# I2CRJ45X16.net
KiCad netlist of a schematic drawn in EAGLE
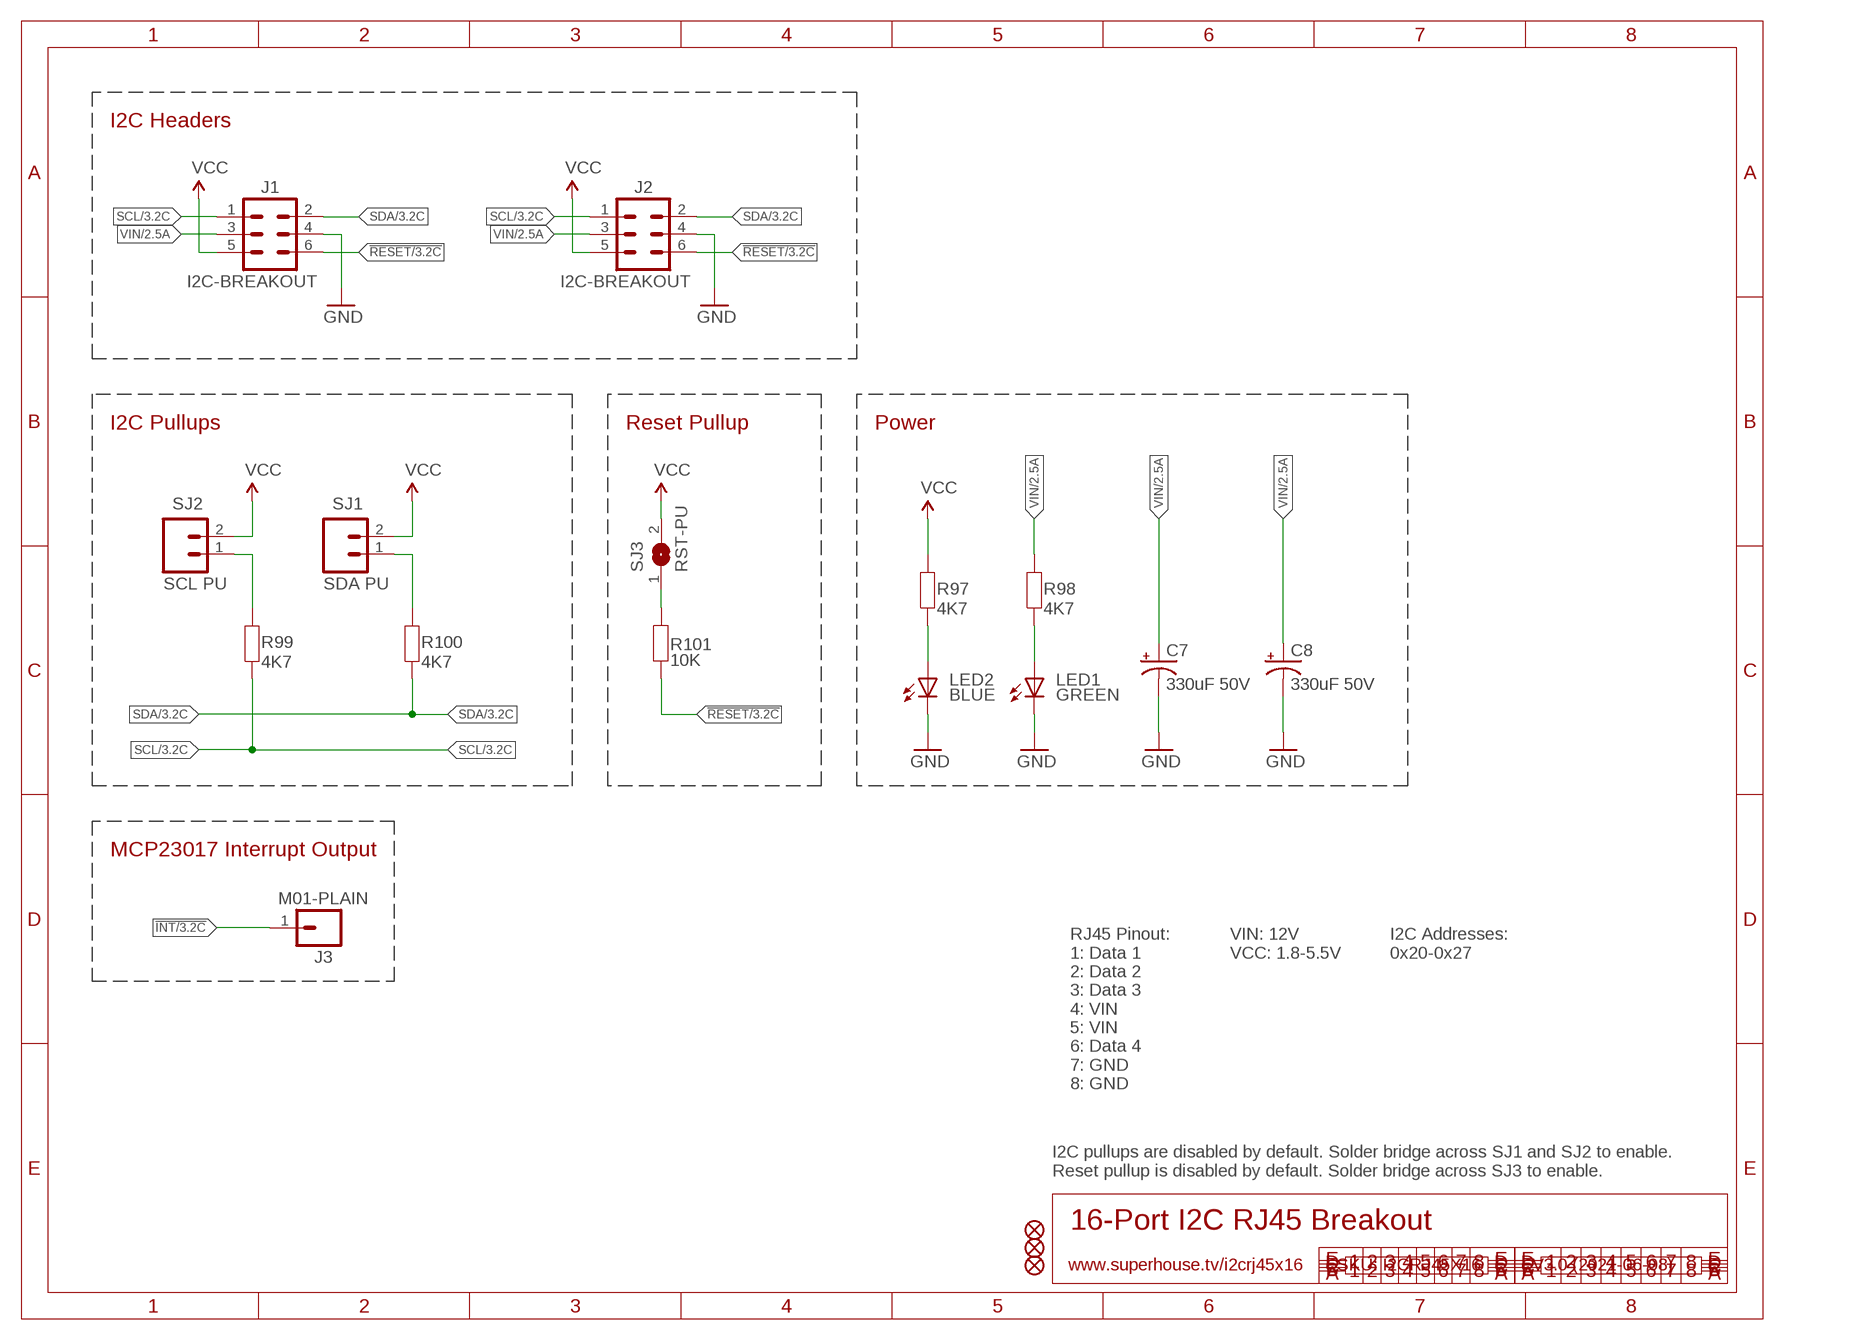
[diagram p0: schematic, sheet 1]
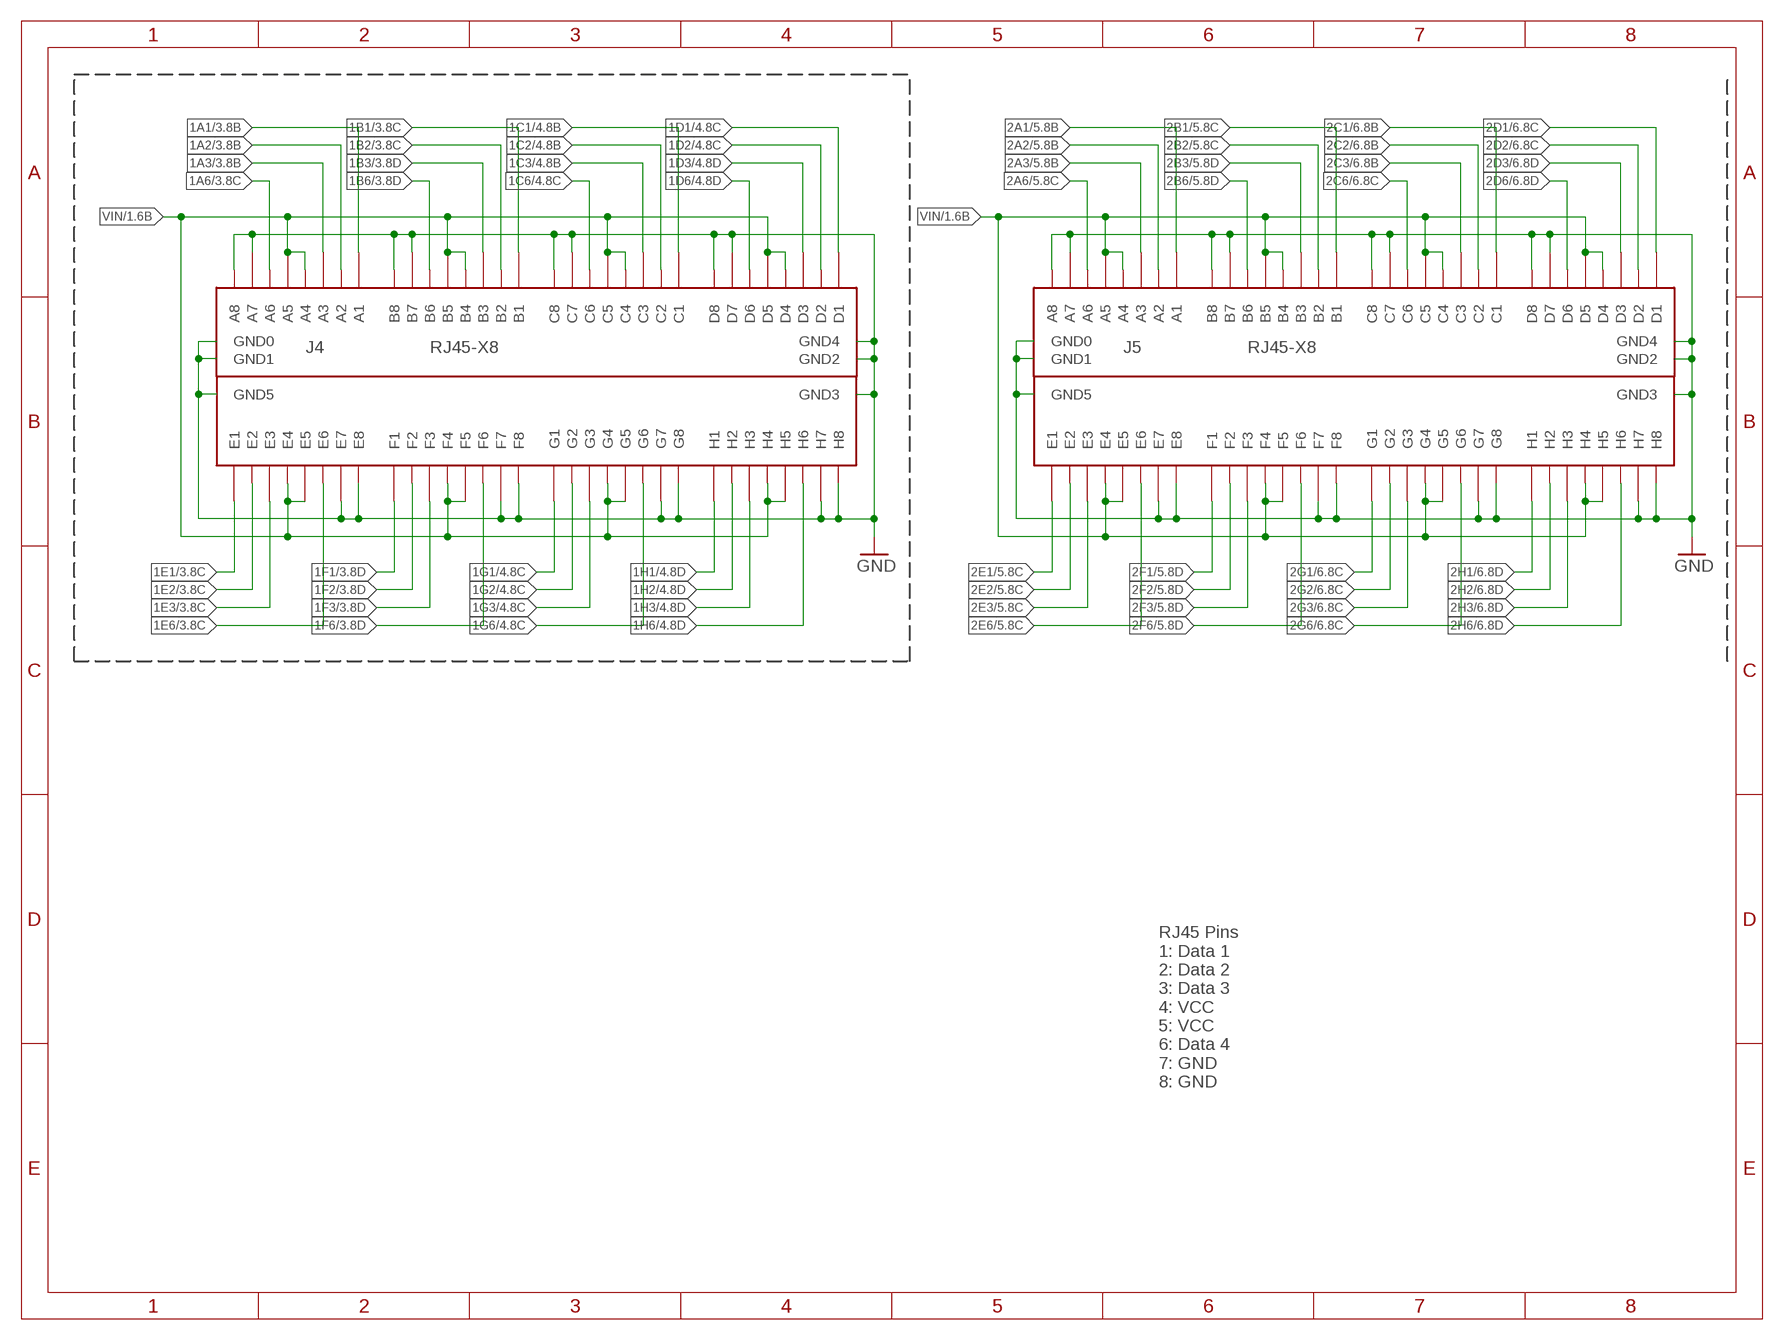
[diagram p1: schematic, sheet 2]
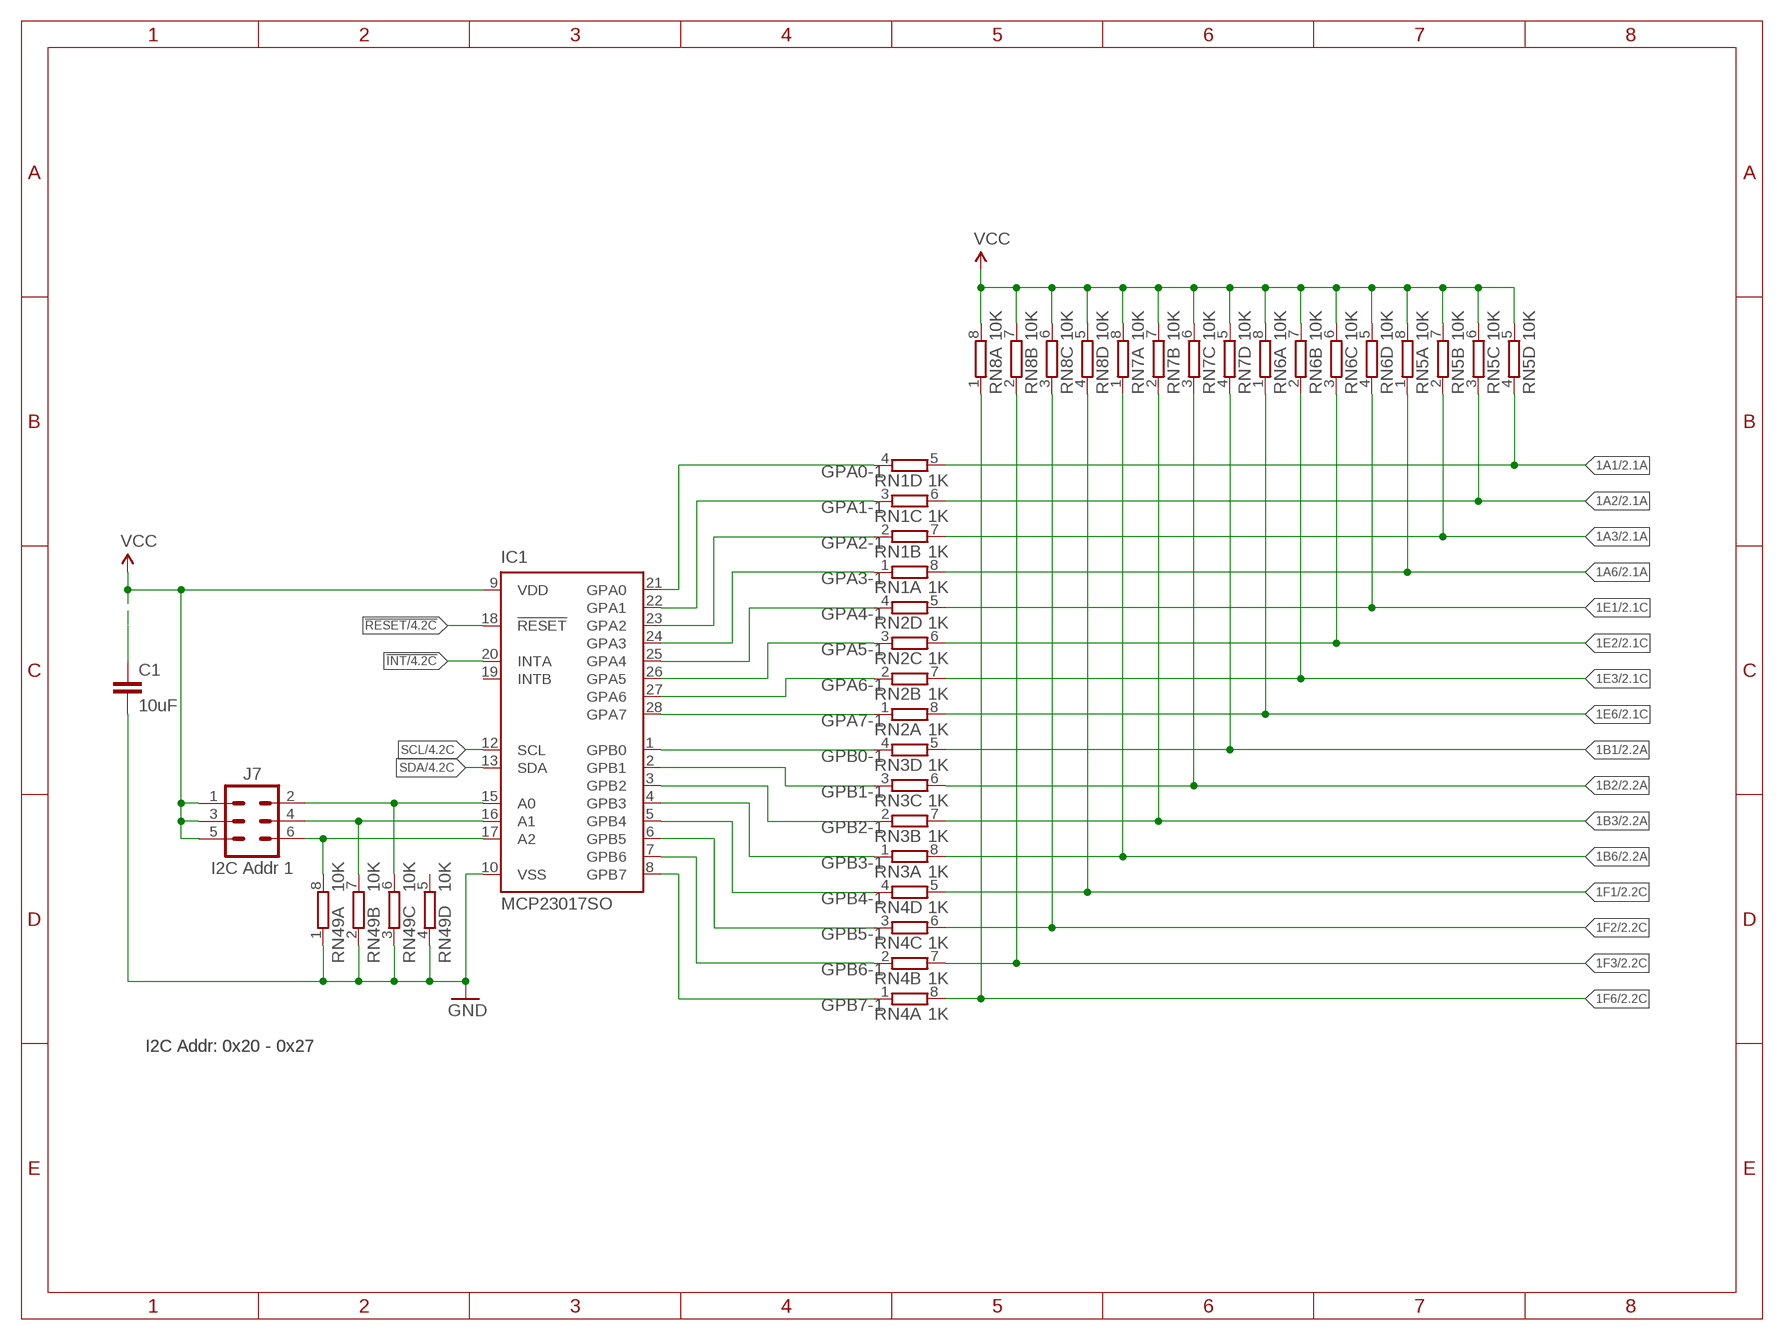
[diagram p2: schematic, sheet 3]
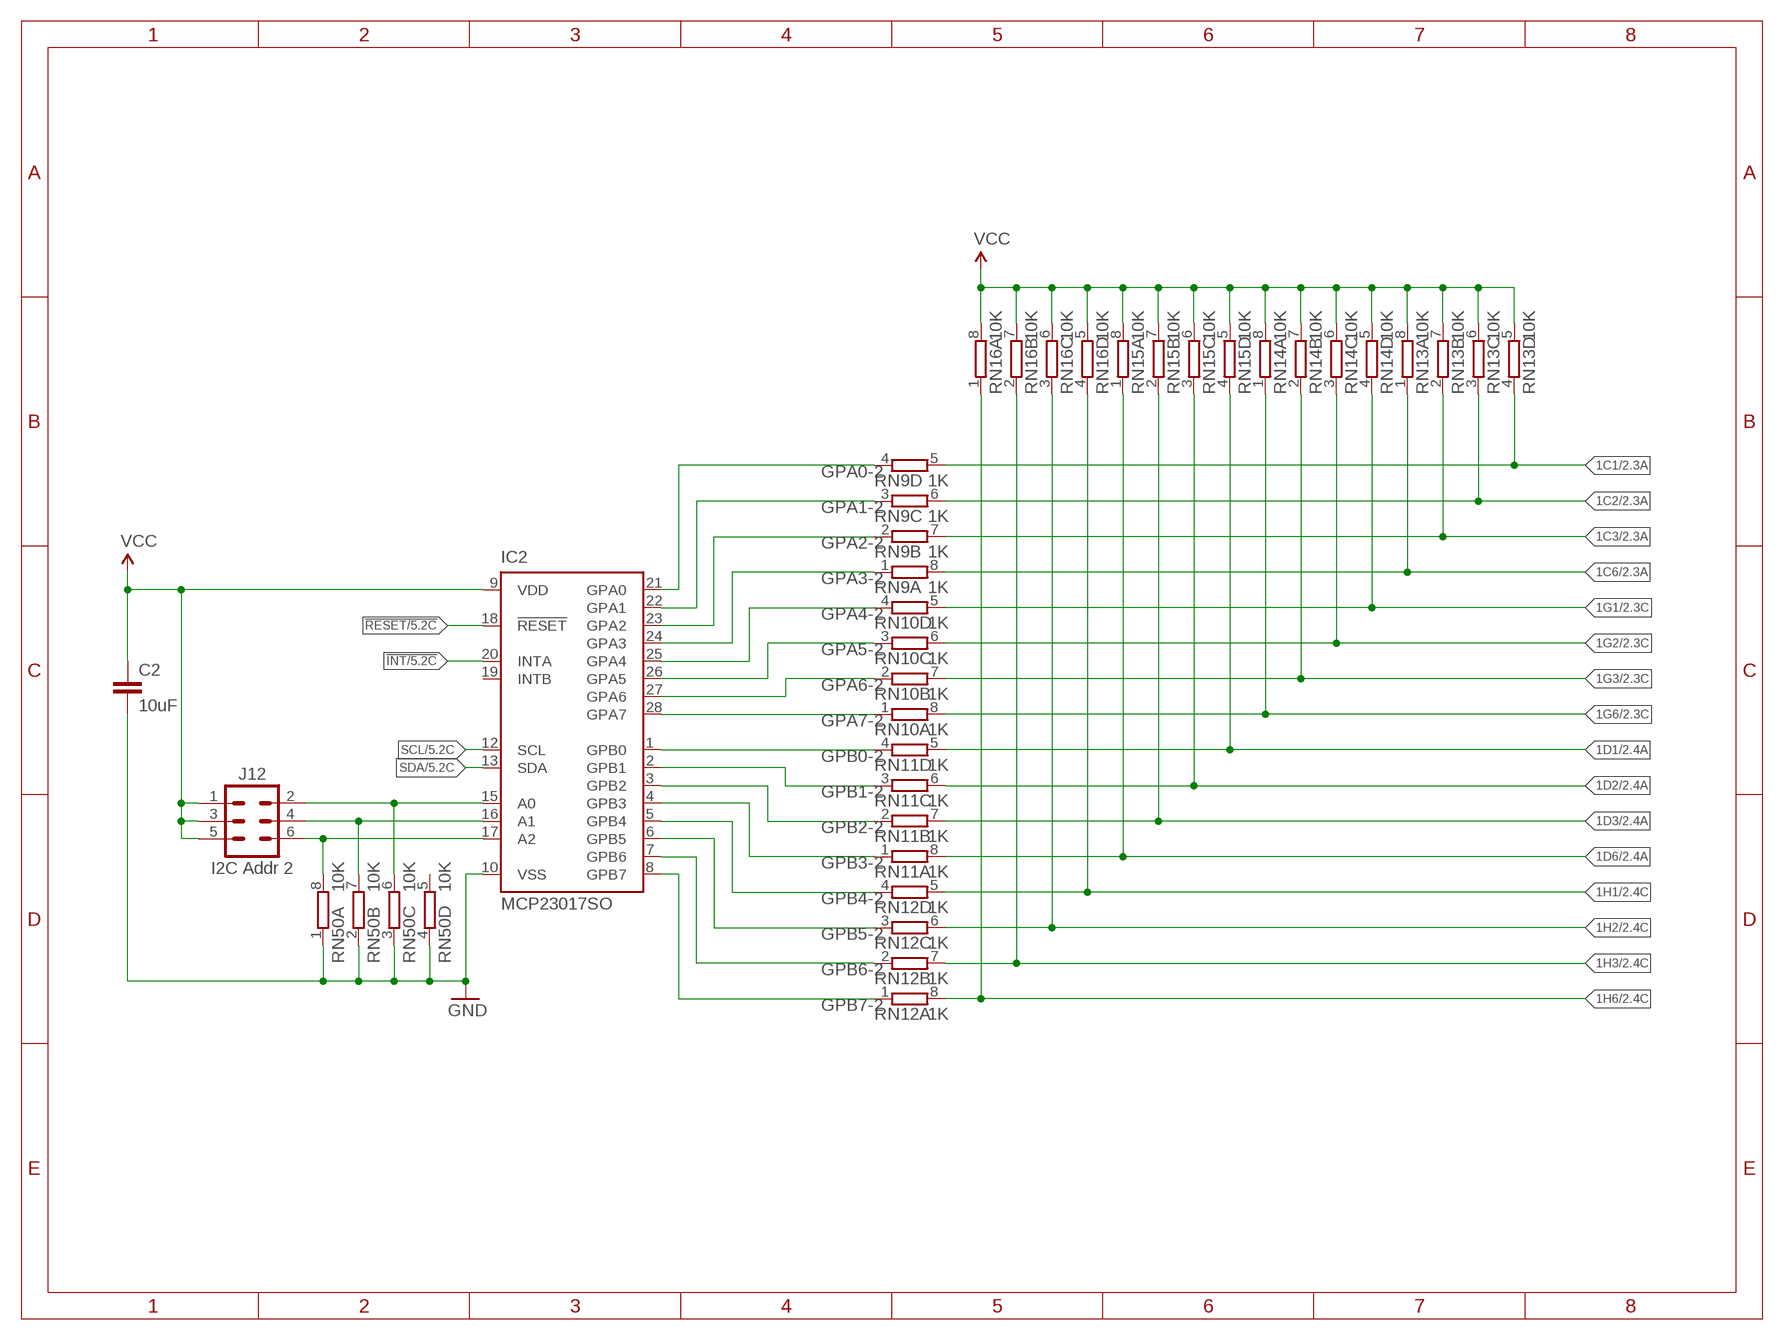
[diagram p3: schematic, sheet 4]
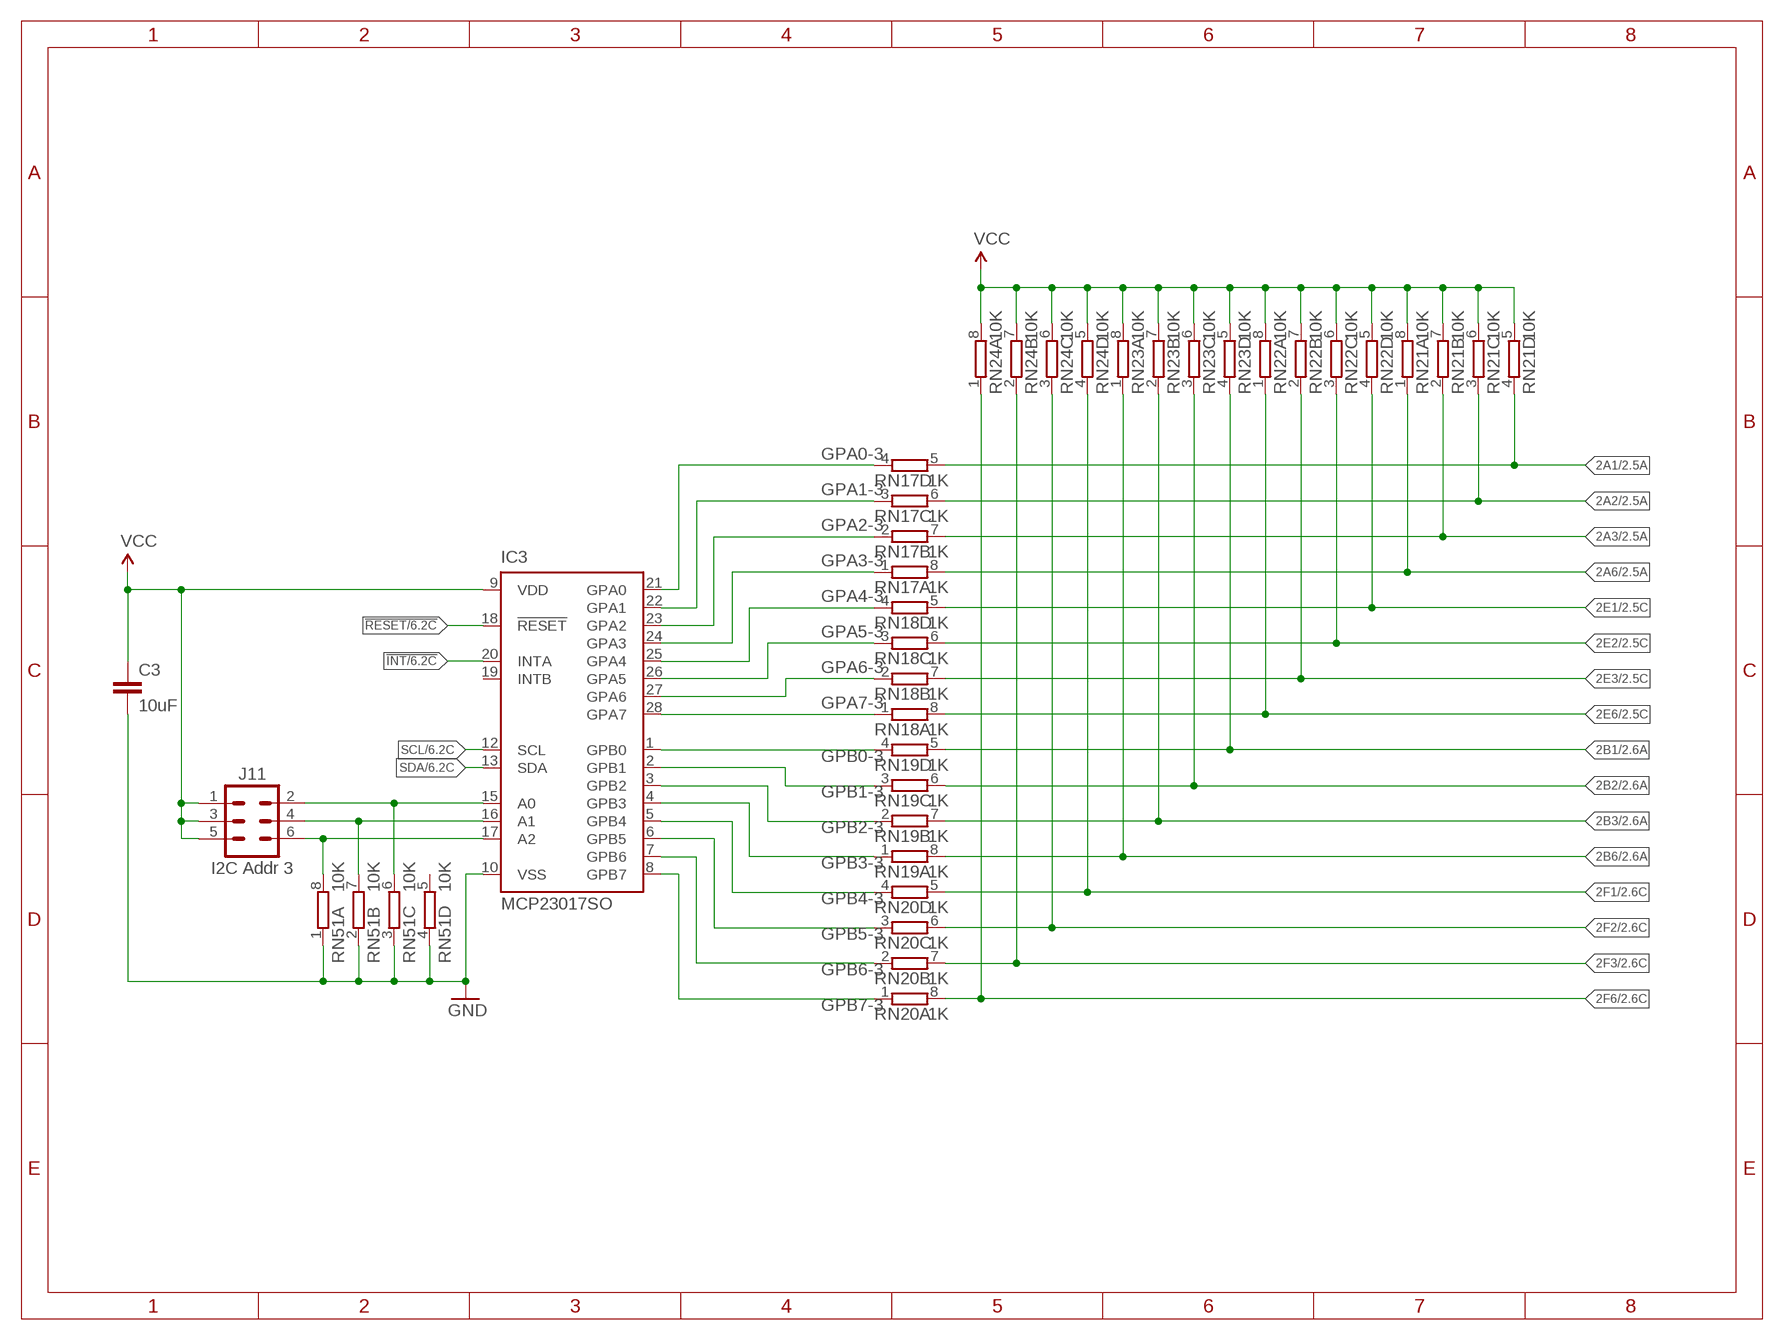
[diagram p4: schematic, sheet 5]
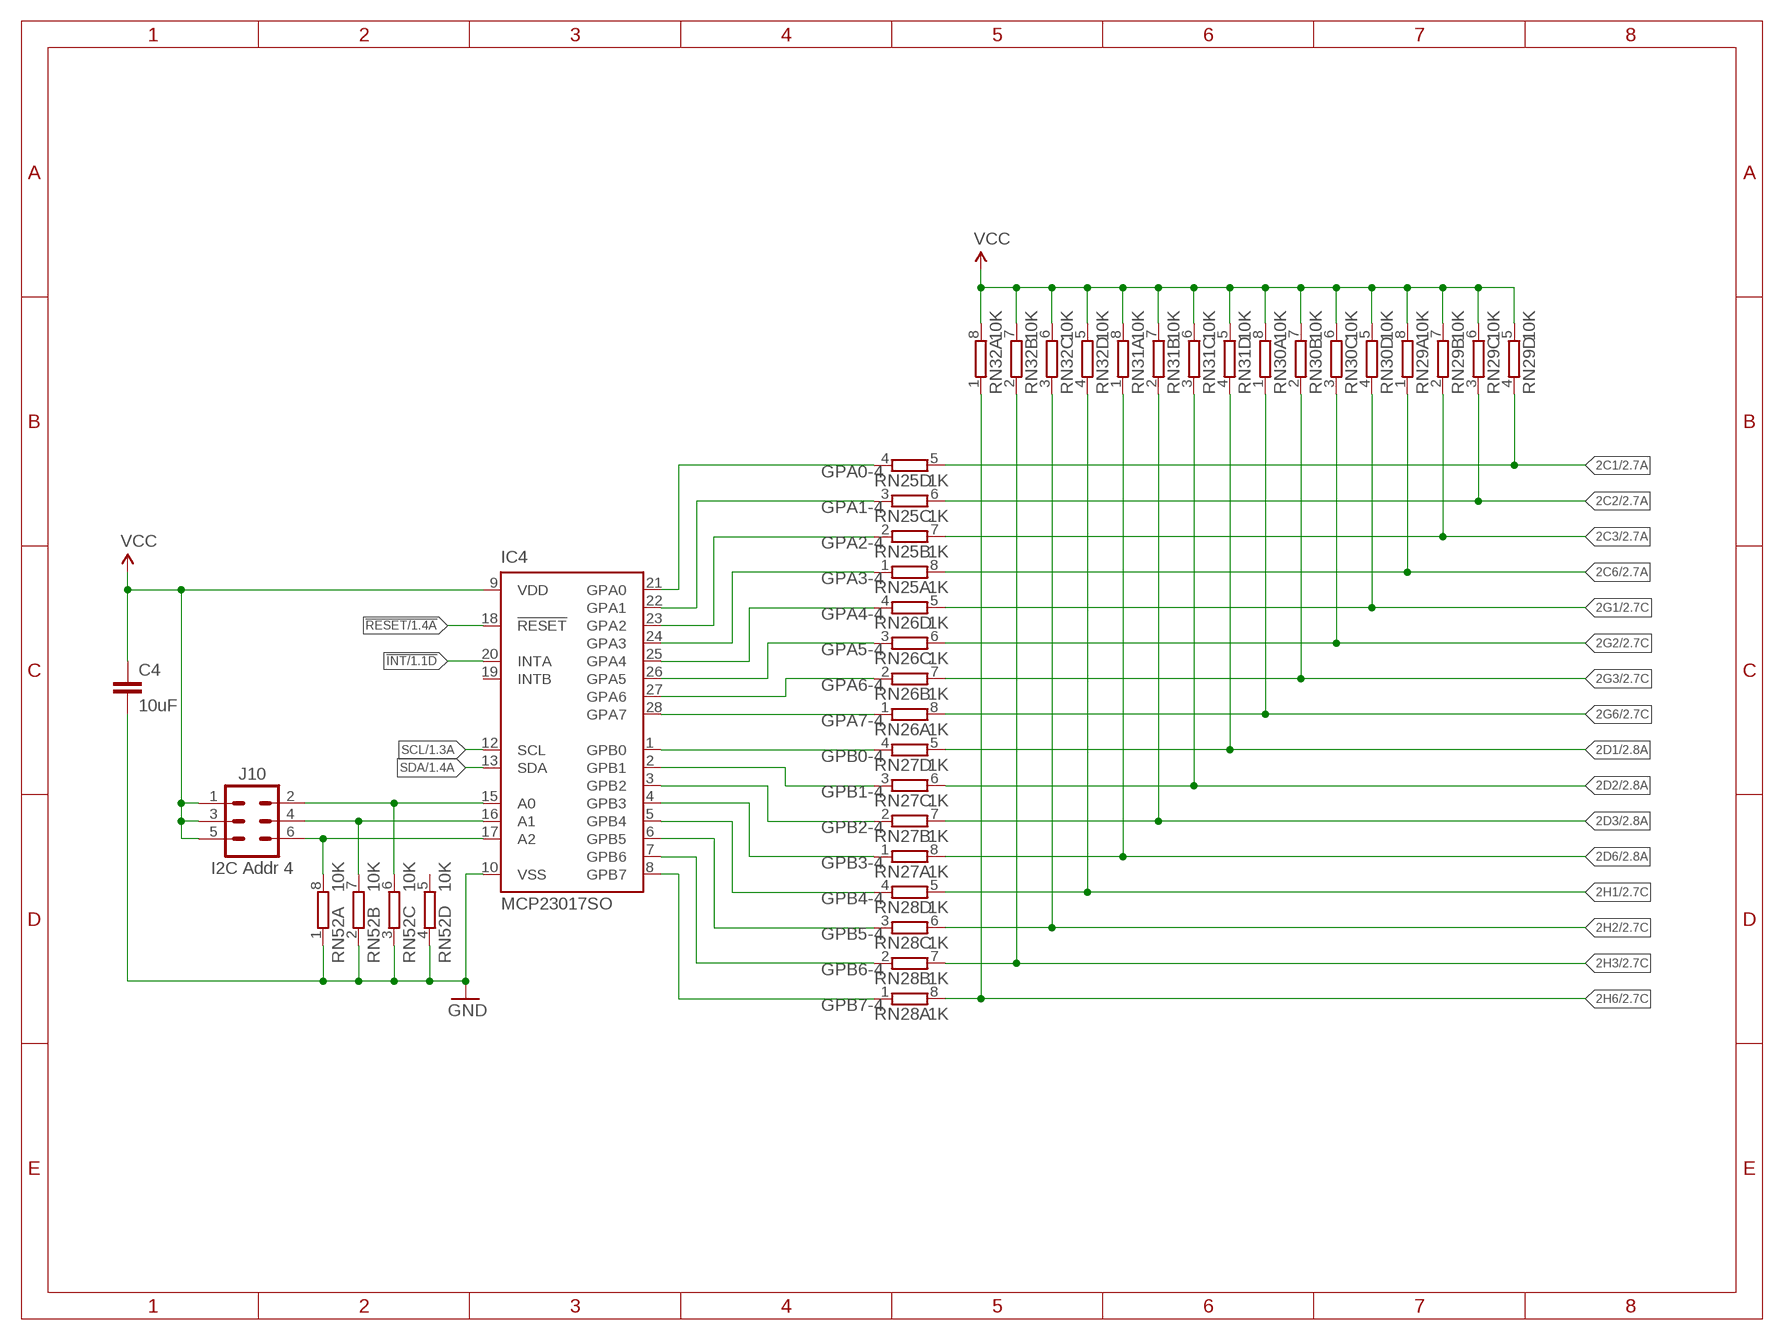
[diagram p5: schematic, sheet 6]

(export (version "E")
  (design (tool "Eeschema 10.0.6"))
  (components
    (comp (ref "C3")
      (value "10uF")
      (footprint "eagle-import:C0805")
      (libsource (lib "eagle-import") (part "CAP0805"))
    )
    (comp (ref "IC3")
      (value "MCP23017SO")
      (footprint "eagle-import:SO28W")
      (libsource (lib "eagle-import") (part "MCP23017SO"))
    )
    (comp (ref "J11")
      (value "I2C Addr 3")
      (footprint "eagle-import:2X03-P")
      (libsource (lib "eagle-import") (part "M02X3-PIN"))
    )
    (comp (ref "RN17")
      (value "1K")
      (footprint "eagle-import:CAY16")
      (libsource (lib "eagle-import") (part "4R-NCAY16"))
    )
    (comp (ref "RN18")
      (value "1K")
      (footprint "eagle-import:CAY16")
      (libsource (lib "eagle-import") (part "4R-NCAY16"))
    )
    (comp (ref "RN19")
      (value "1K")
      (footprint "eagle-import:CAY16")
      (libsource (lib "eagle-import") (part "4R-NCAY16"))
    )
    (comp (ref "RN20")
      (value "1K")
      (footprint "eagle-import:CAY16")
      (libsource (lib "eagle-import") (part "4R-NCAY16"))
    )
    (comp (ref "RN21")
      (value "10K")
      (footprint "eagle-import:CAY16")
      (libsource (lib "eagle-import") (part "4R-NCAY16"))
    )
    (comp (ref "RN22")
      (value "10K")
      (footprint "eagle-import:CAY16")
      (libsource (lib "eagle-import") (part "4R-NCAY16"))
    )
    (comp (ref "RN23")
      (value "10K")
      (footprint "eagle-import:CAY16")
      (libsource (lib "eagle-import") (part "4R-NCAY16"))
    )
    (comp (ref "RN24")
      (value "10K")
      (footprint "eagle-import:CAY16")
      (libsource (lib "eagle-import") (part "4R-NCAY16"))
    )
    (comp (ref "RN51")
      (value "10K")
      (footprint "eagle-import:CAY16")
      (libsource (lib "eagle-import") (part "4R-NCAY16"))
    )
    (comp (ref "C4")
      (value "10uF")
      (footprint "eagle-import:C0805")
      (libsource (lib "eagle-import") (part "CAP0805"))
    )
    (comp (ref "IC4")
      (value "MCP23017SO")
      (footprint "eagle-import:SO28W")
      (libsource (lib "eagle-import") (part "MCP23017SO"))
    )
    (comp (ref "J10")
      (value "I2C Addr 4")
      (footprint "eagle-import:2X03-P")
      (libsource (lib "eagle-import") (part "M02X3-PIN"))
    )
    (comp (ref "RN25")
      (value "1K")
      (footprint "eagle-import:CAY16")
      (libsource (lib "eagle-import") (part "4R-NCAY16"))
    )
    (comp (ref "RN26")
      (value "1K")
      (footprint "eagle-import:CAY16")
      (libsource (lib "eagle-import") (part "4R-NCAY16"))
    )
    (comp (ref "RN27")
      (value "1K")
      (footprint "eagle-import:CAY16")
      (libsource (lib "eagle-import") (part "4R-NCAY16"))
    )
    (comp (ref "RN28")
      (value "1K")
      (footprint "eagle-import:CAY16")
      (libsource (lib "eagle-import") (part "4R-NCAY16"))
    )
    (comp (ref "RN29")
      (value "10K")
      (footprint "eagle-import:CAY16")
      (libsource (lib "eagle-import") (part "4R-NCAY16"))
    )
    (comp (ref "RN30")
      (value "10K")
      (footprint "eagle-import:CAY16")
      (libsource (lib "eagle-import") (part "4R-NCAY16"))
    )
    (comp (ref "RN31")
      (value "10K")
      (footprint "eagle-import:CAY16")
      (libsource (lib "eagle-import") (part "4R-NCAY16"))
    )
    (comp (ref "RN32")
      (value "10K")
      (footprint "eagle-import:CAY16")
      (libsource (lib "eagle-import") (part "4R-NCAY16"))
    )
    (comp (ref "RN52")
      (value "10K")
      (footprint "eagle-import:CAY16")
      (libsource (lib "eagle-import") (part "4R-NCAY16"))
    )
    (comp (ref "C7")
      (value "330uF 50V")
      (footprint "eagle-import:PANASONIC_G")
      (libsource (lib "eagle-import") (part "CAP_POLG"))
    )
    (comp (ref "C8")
      (value "330uF 50V")
      (footprint "eagle-import:PANASONIC_G")
      (libsource (lib "eagle-import") (part "CAP_POLG"))
    )
    (comp (ref "FID1")
      (value "FIDUCIAL1X2.5")
      (footprint "eagle-import:FIDUCIAL-1X2.5")
      (libsource (lib "eagle-import") (part "FIDUCIAL1X2.5"))
    )
    (comp (ref "FID2")
      (value "FIDUCIAL1X2.5")
      (footprint "eagle-import:FIDUCIAL-1X2.5")
      (libsource (lib "eagle-import") (part "FIDUCIAL1X2.5"))
    )
    (comp (ref "FID3")
      (value "FIDUCIAL1X2.5")
      (footprint "eagle-import:FIDUCIAL-1X2.5")
      (libsource (lib "eagle-import") (part "FIDUCIAL1X2.5"))
    )
    (comp (ref "J1")
      (value "I2C-BREAKOUT")
      (footprint "eagle-import:2X3-2.54-SHROUDED")
      (libsource (lib "eagle-import") (part "M02X3-SHROUDED"))
    )
    (comp (ref "J2")
      (value "I2C-BREAKOUT")
      (footprint "eagle-import:2X3-2.54-SHROUDED")
      (libsource (lib "eagle-import") (part "M02X3-SHROUDED"))
    )
    (comp (ref "J3")
      (value "M01-PLAIN")
      (footprint "eagle-import:1X01")
      (libsource (lib "eagle-import") (part "M01-PLAIN"))
    )
    (comp (ref "LED1")
      (value "GREEN")
      (footprint "eagle-import:LED-0603")
      (libsource (lib "eagle-import") (part "LED0603"))
    )
    (comp (ref "LED2")
      (value "BLUE")
      (footprint "eagle-import:LED-0603")
      (libsource (lib "eagle-import") (part "LED0603"))
    )
    (comp (ref "R97")
      (value "4K7")
      (footprint "eagle-import:R0603")
      (libsource (lib "eagle-import") (part "RESISTOR0603"))
    )
    (comp (ref "R98")
      (value "4K7")
      (footprint "eagle-import:R0603")
      (libsource (lib "eagle-import") (part "RESISTOR0603"))
    )
    (comp (ref "R99")
      (value "4K7")
      (footprint "eagle-import:R0603")
      (libsource (lib "eagle-import") (part "RESISTOR0603"))
    )
    (comp (ref "R100")
      (value "4K7")
      (footprint "eagle-import:R0603")
      (libsource (lib "eagle-import") (part "RESISTOR0603"))
    )
    (comp (ref "R101")
      (value "10K")
      (footprint "eagle-import:R0603")
      (libsource (lib "eagle-import") (part "RESISTOR0603"))
    )
    (comp (ref "SJ1")
      (value "SDA PU")
      (footprint "eagle-import:1X02-P")
      (libsource (lib "eagle-import") (part "M02-PIN"))
    )
    (comp (ref "SJ2")
      (value "SCL PU")
      (footprint "eagle-import:1X02-P")
      (libsource (lib "eagle-import") (part "M02-PIN"))
    )
    (comp (ref "SJ3")
      (value "RST-PU")
      (footprint "eagle-import:SJ")
      (libsource (lib "eagle-import") (part "SJ-NORMAL"))
    )
    (comp (ref "C2")
      (value "10uF")
      (footprint "eagle-import:C0805")
      (libsource (lib "eagle-import") (part "CAP0805"))
    )
    (comp (ref "IC2")
      (value "MCP23017SO")
      (footprint "eagle-import:SO28W")
      (libsource (lib "eagle-import") (part "MCP23017SO"))
    )
    (comp (ref "J12")
      (value "I2C Addr 2")
      (footprint "eagle-import:2X03-P")
      (libsource (lib "eagle-import") (part "M02X3-PIN"))
    )
    (comp (ref "RN9")
      (value "1K")
      (footprint "eagle-import:CAY16")
      (libsource (lib "eagle-import") (part "4R-NCAY16"))
    )
    (comp (ref "RN10")
      (value "1K")
      (footprint "eagle-import:CAY16")
      (libsource (lib "eagle-import") (part "4R-NCAY16"))
    )
    (comp (ref "RN11")
      (value "1K")
      (footprint "eagle-import:CAY16")
      (libsource (lib "eagle-import") (part "4R-NCAY16"))
    )
    (comp (ref "RN12")
      (value "1K")
      (footprint "eagle-import:CAY16")
      (libsource (lib "eagle-import") (part "4R-NCAY16"))
    )
    (comp (ref "RN13")
      (value "10K")
      (footprint "eagle-import:CAY16")
      (libsource (lib "eagle-import") (part "4R-NCAY16"))
    )
    (comp (ref "RN14")
      (value "10K")
      (footprint "eagle-import:CAY16")
      (libsource (lib "eagle-import") (part "4R-NCAY16"))
    )
    (comp (ref "RN15")
      (value "10K")
      (footprint "eagle-import:CAY16")
      (libsource (lib "eagle-import") (part "4R-NCAY16"))
    )
    (comp (ref "RN16")
      (value "10K")
      (footprint "eagle-import:CAY16")
      (libsource (lib "eagle-import") (part "4R-NCAY16"))
    )
    (comp (ref "RN50")
      (value "10K")
      (footprint "eagle-import:CAY16")
      (libsource (lib "eagle-import") (part "4R-NCAY16"))
    )
    (comp (ref "C1")
      (value "10uF")
      (footprint "eagle-import:C0805")
      (libsource (lib "eagle-import") (part "CAP0805"))
    )
    (comp (ref "IC1")
      (value "MCP23017SO")
      (footprint "eagle-import:SO28W")
      (libsource (lib "eagle-import") (part "MCP23017SO"))
    )
    (comp (ref "J7")
      (value "I2C Addr 1")
      (footprint "eagle-import:2X03-P")
      (libsource (lib "eagle-import") (part "M02X3-PIN"))
    )
    (comp (ref "RN1")
      (value "1K")
      (footprint "eagle-import:CAY16")
      (libsource (lib "eagle-import") (part "4R-NCAY16"))
    )
    (comp (ref "RN2")
      (value "1K")
      (footprint "eagle-import:CAY16")
      (libsource (lib "eagle-import") (part "4R-NCAY16"))
    )
    (comp (ref "RN3")
      (value "1K")
      (footprint "eagle-import:CAY16")
      (libsource (lib "eagle-import") (part "4R-NCAY16"))
    )
    (comp (ref "RN4")
      (value "1K")
      (footprint "eagle-import:CAY16")
      (libsource (lib "eagle-import") (part "4R-NCAY16"))
    )
    (comp (ref "RN5")
      (value "10K")
      (footprint "eagle-import:CAY16")
      (libsource (lib "eagle-import") (part "4R-NCAY16"))
    )
    (comp (ref "RN6")
      (value "10K")
      (footprint "eagle-import:CAY16")
      (libsource (lib "eagle-import") (part "4R-NCAY16"))
    )
    (comp (ref "RN7")
      (value "10K")
      (footprint "eagle-import:CAY16")
      (libsource (lib "eagle-import") (part "4R-NCAY16"))
    )
    (comp (ref "RN8")
      (value "10K")
      (footprint "eagle-import:CAY16")
      (libsource (lib "eagle-import") (part "4R-NCAY16"))
    )
    (comp (ref "RN49")
      (value "10K")
      (footprint "eagle-import:CAY16")
      (libsource (lib "eagle-import") (part "4R-NCAY16"))
    )
    (comp (ref "J4")
      (value "RJ45-X8")
      (footprint "eagle-import:RJ45-2X4")
      (libsource (lib "eagle-import") (part "RJ45-X8"))
    )
    (comp (ref "J5")
      (value "RJ45-X8")
      (footprint "eagle-import:RJ45-2X4")
      (libsource (lib "eagle-import") (part "RJ45-X8"))
    )
  )
  (nets
    (net (code "1") (name "1A1") (class "Default")
      (node (ref "J4") (pin "A1") (pinfunction "A1_A1") (pintype "bidirectional"))
      (node (ref "RN1") (pin "5") (pinfunction "2_5") (pintype "passive"))
      (node (ref "RN5") (pin "4") (pinfunction "1_4") (pintype "passive"))
    )
    (net (code "2") (name "1A2") (class "Default")
      (node (ref "J4") (pin "A2") (pinfunction "A2_A2") (pintype "bidirectional"))
      (node (ref "RN1") (pin "6") (pinfunction "2_6") (pintype "passive"))
      (node (ref "RN5") (pin "3") (pinfunction "1_3") (pintype "passive"))
    )
    (net (code "3") (name "1A3") (class "Default")
      (node (ref "J4") (pin "A3") (pinfunction "A3_A3") (pintype "bidirectional"))
      (node (ref "RN1") (pin "7") (pinfunction "2_7") (pintype "passive"))
      (node (ref "RN5") (pin "2") (pinfunction "1_2") (pintype "passive"))
    )
    (net (code "4") (name "1A6") (class "Default")
      (node (ref "J4") (pin "A6") (pinfunction "A6_A6") (pintype "bidirectional"))
      (node (ref "RN1") (pin "8") (pinfunction "2_8") (pintype "passive"))
      (node (ref "RN5") (pin "1") (pinfunction "1_1") (pintype "passive"))
    )
    (net (code "5") (name "1B1") (class "Default")
      (node (ref "J4") (pin "B1") (pinfunction "B1_B1") (pintype "bidirectional"))
      (node (ref "RN3") (pin "5") (pinfunction "2_5") (pintype "passive"))
      (node (ref "RN7") (pin "4") (pinfunction "1_4") (pintype "passive"))
    )
    (net (code "6") (name "1B2") (class "Default")
      (node (ref "J4") (pin "B2") (pinfunction "B2_B2") (pintype "bidirectional"))
      (node (ref "RN3") (pin "6") (pinfunction "2_6") (pintype "passive"))
      (node (ref "RN7") (pin "3") (pinfunction "1_3") (pintype "passive"))
    )
    (net (code "7") (name "1B3") (class "Default")
      (node (ref "J4") (pin "B3") (pinfunction "B3_B3") (pintype "bidirectional"))
      (node (ref "RN3") (pin "7") (pinfunction "2_7") (pintype "passive"))
      (node (ref "RN7") (pin "2") (pinfunction "1_2") (pintype "passive"))
    )
    (net (code "8") (name "1B6") (class "Default")
      (node (ref "J4") (pin "B6") (pinfunction "B6_B6") (pintype "bidirectional"))
      (node (ref "RN3") (pin "8") (pinfunction "2_8") (pintype "passive"))
      (node (ref "RN7") (pin "1") (pinfunction "1_1") (pintype "passive"))
    )
    (net (code "9") (name "1C1") (class "Default")
      (node (ref "J4") (pin "C1") (pinfunction "C1_C1") (pintype "bidirectional"))
      (node (ref "RN13") (pin "4") (pinfunction "1_4") (pintype "passive"))
      (node (ref "RN9") (pin "5") (pinfunction "2_5") (pintype "passive"))
    )
    (net (code "10") (name "1C2") (class "Default")
      (node (ref "J4") (pin "C2") (pinfunction "C2_C2") (pintype "bidirectional"))
      (node (ref "RN13") (pin "3") (pinfunction "1_3") (pintype "passive"))
      (node (ref "RN9") (pin "6") (pinfunction "2_6") (pintype "passive"))
    )
    (net (code "11") (name "1C3") (class "Default")
      (node (ref "J4") (pin "C3") (pinfunction "C3_C3") (pintype "bidirectional"))
      (node (ref "RN13") (pin "2") (pinfunction "1_2") (pintype "passive"))
      (node (ref "RN9") (pin "7") (pinfunction "2_7") (pintype "passive"))
    )
    (net (code "12") (name "1C6") (class "Default")
      (node (ref "J4") (pin "C6") (pinfunction "C6_C6") (pintype "bidirectional"))
      (node (ref "RN13") (pin "1") (pinfunction "1_1") (pintype "passive"))
      (node (ref "RN9") (pin "8") (pinfunction "2_8") (pintype "passive"))
    )
    (net (code "13") (name "1D1") (class "Default")
      (node (ref "J4") (pin "D1") (pinfunction "D1_D1") (pintype "bidirectional"))
      (node (ref "RN11") (pin "5") (pinfunction "2_5") (pintype "passive"))
      (node (ref "RN15") (pin "4") (pinfunction "1_4") (pintype "passive"))
    )
    (net (code "14") (name "1D2") (class "Default")
      (node (ref "J4") (pin "D2") (pinfunction "D2_D2") (pintype "bidirectional"))
      (node (ref "RN11") (pin "6") (pinfunction "2_6") (pintype "passive"))
      (node (ref "RN15") (pin "3") (pinfunction "1_3") (pintype "passive"))
    )
    (net (code "15") (name "1D3") (class "Default")
      (node (ref "J4") (pin "D3") (pinfunction "D3_D3") (pintype "bidirectional"))
      (node (ref "RN11") (pin "7") (pinfunction "2_7") (pintype "passive"))
      (node (ref "RN15") (pin "2") (pinfunction "1_2") (pintype "passive"))
    )
    (net (code "16") (name "1D6") (class "Default")
      (node (ref "J4") (pin "D6") (pinfunction "D6_D6") (pintype "bidirectional"))
      (node (ref "RN11") (pin "8") (pinfunction "2_8") (pintype "passive"))
      (node (ref "RN15") (pin "1") (pinfunction "1_1") (pintype "passive"))
    )
    (net (code "17") (name "1E1") (class "Default")
      (node (ref "J4") (pin "E1") (pinfunction "E1_E1") (pintype "bidirectional"))
      (node (ref "RN2") (pin "5") (pinfunction "2_5") (pintype "passive"))
      (node (ref "RN6") (pin "4") (pinfunction "1_4") (pintype "passive"))
    )
    (net (code "18") (name "1E2") (class "Default")
      (node (ref "J4") (pin "E2") (pinfunction "E2_E2") (pintype "bidirectional"))
      (node (ref "RN2") (pin "6") (pinfunction "2_6") (pintype "passive"))
      (node (ref "RN6") (pin "3") (pinfunction "1_3") (pintype "passive"))
    )
    (net (code "19") (name "1E3") (class "Default")
      (node (ref "J4") (pin "E3") (pinfunction "E3_E3") (pintype "bidirectional"))
      (node (ref "RN2") (pin "7") (pinfunction "2_7") (pintype "passive"))
      (node (ref "RN6") (pin "2") (pinfunction "1_2") (pintype "passive"))
    )
    (net (code "20") (name "1E6") (class "Default")
      (node (ref "J4") (pin "E6") (pinfunction "E6_E6") (pintype "bidirectional"))
      (node (ref "RN2") (pin "8") (pinfunction "2_8") (pintype "passive"))
      (node (ref "RN6") (pin "1") (pinfunction "1_1") (pintype "passive"))
    )
    (net (code "21") (name "1F1") (class "Default")
      (node (ref "J4") (pin "F1") (pinfunction "F1_F1") (pintype "bidirectional"))
      (node (ref "RN4") (pin "5") (pinfunction "2_5") (pintype "passive"))
      (node (ref "RN8") (pin "4") (pinfunction "1_4") (pintype "passive"))
    )
    (net (code "22") (name "1F2") (class "Default")
      (node (ref "J4") (pin "F2") (pinfunction "F2_F2") (pintype "bidirectional"))
      (node (ref "RN4") (pin "6") (pinfunction "2_6") (pintype "passive"))
      (node (ref "RN8") (pin "3") (pinfunction "1_3") (pintype "passive"))
    )
    (net (code "23") (name "1F3") (class "Default")
      (node (ref "J4") (pin "F3") (pinfunction "F3_F3") (pintype "bidirectional"))
      (node (ref "RN4") (pin "7") (pinfunction "2_7") (pintype "passive"))
      (node (ref "RN8") (pin "2") (pinfunction "1_2") (pintype "passive"))
    )
    (net (code "24") (name "1F6") (class "Default")
      (node (ref "J4") (pin "F6") (pinfunction "F6_F6") (pintype "bidirectional"))
      (node (ref "RN4") (pin "8") (pinfunction "2_8") (pintype "passive"))
      (node (ref "RN8") (pin "1") (pinfunction "1_1") (pintype "passive"))
    )
    (net (code "25") (name "1G1") (class "Default")
      (node (ref "J4") (pin "G1") (pinfunction "G1_G1") (pintype "bidirectional"))
      (node (ref "RN10") (pin "5") (pinfunction "2_5") (pintype "passive"))
      (node (ref "RN14") (pin "4") (pinfunction "1_4") (pintype "passive"))
    )
    (net (code "26") (name "1G2") (class "Default")
      (node (ref "J4") (pin "G2") (pinfunction "G2_G2") (pintype "bidirectional"))
      (node (ref "RN10") (pin "6") (pinfunction "2_6") (pintype "passive"))
      (node (ref "RN14") (pin "3") (pinfunction "1_3") (pintype "passive"))
    )
    (net (code "27") (name "1G3") (class "Default")
      (node (ref "J4") (pin "G3") (pinfunction "G3_G3") (pintype "bidirectional"))
      (node (ref "RN10") (pin "7") (pinfunction "2_7") (pintype "passive"))
      (node (ref "RN14") (pin "2") (pinfunction "1_2") (pintype "passive"))
    )
    (net (code "28") (name "1G6") (class "Default")
      (node (ref "J4") (pin "G6") (pinfunction "G6_G6") (pintype "bidirectional"))
      (node (ref "RN10") (pin "8") (pinfunction "2_8") (pintype "passive"))
      (node (ref "RN14") (pin "1") (pinfunction "1_1") (pintype "passive"))
    )
    (net (code "29") (name "1H1") (class "Default")
      (node (ref "J4") (pin "H1") (pinfunction "H1_H1") (pintype "bidirectional"))
      (node (ref "RN12") (pin "5") (pinfunction "2_5") (pintype "passive"))
      (node (ref "RN16") (pin "4") (pinfunction "1_4") (pintype "passive"))
    )
    (net (code "30") (name "1H2") (class "Default")
      (node (ref "J4") (pin "H2") (pinfunction "H2_H2") (pintype "bidirectional"))
      (node (ref "RN12") (pin "6") (pinfunction "2_6") (pintype "passive"))
      (node (ref "RN16") (pin "3") (pinfunction "1_3") (pintype "passive"))
    )
    (net (code "31") (name "1H3") (class "Default")
      (node (ref "J4") (pin "H3") (pinfunction "H3_H3") (pintype "bidirectional"))
      (node (ref "RN12") (pin "7") (pinfunction "2_7") (pintype "passive"))
      (node (ref "RN16") (pin "2") (pinfunction "1_2") (pintype "passive"))
    )
    (net (code "32") (name "1H6") (class "Default")
      (node (ref "J4") (pin "H6") (pinfunction "H6_H6") (pintype "bidirectional"))
      (node (ref "RN12") (pin "8") (pinfunction "2_8") (pintype "passive"))
      (node (ref "RN16") (pin "1") (pinfunction "1_1") (pintype "passive"))
    )
    (net (code "33") (name "2A1") (class "Default")
      (node (ref "J5") (pin "A1") (pinfunction "A1_A1") (pintype "bidirectional"))
      (node (ref "RN17") (pin "5") (pinfunction "2_5") (pintype "passive"))
      (node (ref "RN21") (pin "4") (pinfunction "1_4") (pintype "passive"))
    )
    (net (code "34") (name "2A2") (class "Default")
      (node (ref "J5") (pin "A2") (pinfunction "A2_A2") (pintype "bidirectional"))
      (node (ref "RN17") (pin "6") (pinfunction "2_6") (pintype "passive"))
      (node (ref "RN21") (pin "3") (pinfunction "1_3") (pintype "passive"))
    )
    (net (code "35") (name "2A3") (class "Default")
      (node (ref "J5") (pin "A3") (pinfunction "A3_A3") (pintype "bidirectional"))
      (node (ref "RN17") (pin "7") (pinfunction "2_7") (pintype "passive"))
      (node (ref "RN21") (pin "2") (pinfunction "1_2") (pintype "passive"))
    )
    (net (code "36") (name "2A6") (class "Default")
      (node (ref "J5") (pin "A6") (pinfunction "A6_A6") (pintype "bidirectional"))
      (node (ref "RN17") (pin "8") (pinfunction "2_8") (pintype "passive"))
      (node (ref "RN21") (pin "1") (pinfunction "1_1") (pintype "passive"))
    )
    (net (code "37") (name "2B1") (class "Default")
      (node (ref "J5") (pin "B1") (pinfunction "B1_B1") (pintype "bidirectional"))
      (node (ref "RN19") (pin "5") (pinfunction "2_5") (pintype "passive"))
      (node (ref "RN23") (pin "4") (pinfunction "1_4") (pintype "passive"))
    )
    (net (code "38") (name "2B2") (class "Default")
      (node (ref "J5") (pin "B2") (pinfunction "B2_B2") (pintype "bidirectional"))
      (node (ref "RN19") (pin "6") (pinfunction "2_6") (pintype "passive"))
      (node (ref "RN23") (pin "3") (pinfunction "1_3") (pintype "passive"))
    )
    (net (code "39") (name "2B3") (class "Default")
      (node (ref "J5") (pin "B3") (pinfunction "B3_B3") (pintype "bidirectional"))
      (node (ref "RN19") (pin "7") (pinfunction "2_7") (pintype "passive"))
      (node (ref "RN23") (pin "2") (pinfunction "1_2") (pintype "passive"))
    )
    (net (code "40") (name "2B6") (class "Default")
      (node (ref "J5") (pin "B6") (pinfunction "B6_B6") (pintype "bidirectional"))
      (node (ref "RN19") (pin "8") (pinfunction "2_8") (pintype "passive"))
      (node (ref "RN23") (pin "1") (pinfunction "1_1") (pintype "passive"))
    )
    (net (code "41") (name "2C1") (class "Default")
      (node (ref "J5") (pin "C1") (pinfunction "C1_C1") (pintype "bidirectional"))
      (node (ref "RN25") (pin "5") (pinfunction "2_5") (pintype "passive"))
      (node (ref "RN29") (pin "4") (pinfunction "1_4") (pintype "passive"))
    )
    (net (code "42") (name "2C2") (class "Default")
      (node (ref "J5") (pin "C2") (pinfunction "C2_C2") (pintype "bidirectional"))
      (node (ref "RN25") (pin "6") (pinfunction "2_6") (pintype "passive"))
      (node (ref "RN29") (pin "3") (pinfunction "1_3") (pintype "passive"))
    )
    (net (code "43") (name "2C3") (class "Default")
      (node (ref "J5") (pin "C3") (pinfunction "C3_C3") (pintype "bidirectional"))
      (node (ref "RN25") (pin "7") (pinfunction "2_7") (pintype "passive"))
      (node (ref "RN29") (pin "2") (pinfunction "1_2") (pintype "passive"))
    )
    (net (code "44") (name "2C6") (class "Default")
      (node (ref "J5") (pin "C6") (pinfunction "C6_C6") (pintype "bidirectional"))
      (node (ref "RN25") (pin "8") (pinfunction "2_8") (pintype "passive"))
      (node (ref "RN29") (pin "1") (pinfunction "1_1") (pintype "passive"))
    )
    (net (code "45") (name "2D1") (class "Default")
      (node (ref "J5") (pin "D1") (pinfunction "D1_D1") (pintype "bidirectional"))
      (node (ref "RN27") (pin "5") (pinfunction "2_5") (pintype "passive"))
      (node (ref "RN31") (pin "4") (pinfunction "1_4") (pintype "passive"))
    )
    (net (code "46") (name "2D2") (class "Default")
      (node (ref "J5") (pin "D2") (pinfunction "D2_D2") (pintype "bidirectional"))
      (node (ref "RN27") (pin "6") (pinfunction "2_6") (pintype "passive"))
      (node (ref "RN31") (pin "3") (pinfunction "1_3") (pintype "passive"))
    )
    (net (code "47") (name "2D3") (class "Default")
      (node (ref "J5") (pin "D3") (pinfunction "D3_D3") (pintype "bidirectional"))
      (node (ref "RN27") (pin "7") (pinfunction "2_7") (pintype "passive"))
      (node (ref "RN31") (pin "2") (pinfunction "1_2") (pintype "passive"))
    )
    (net (code "48") (name "2D6") (class "Default")
      (node (ref "J5") (pin "D6") (pinfunction "D6_D6") (pintype "bidirectional"))
      (node (ref "RN27") (pin "8") (pinfunction "2_8") (pintype "passive"))
      (node (ref "RN31") (pin "1") (pinfunction "1_1") (pintype "passive"))
    )
    (net (code "49") (name "2E1") (class "Default")
      (node (ref "J5") (pin "E1") (pinfunction "E1_E1") (pintype "bidirectional"))
      (node (ref "RN18") (pin "5") (pinfunction "2_5") (pintype "passive"))
      (node (ref "RN22") (pin "4") (pinfunction "1_4") (pintype "passive"))
    )
    (net (code "50") (name "2E2") (class "Default")
      (node (ref "J5") (pin "E2") (pinfunction "E2_E2") (pintype "bidirectional"))
      (node (ref "RN18") (pin "6") (pinfunction "2_6") (pintype "passive"))
      (node (ref "RN22") (pin "3") (pinfunction "1_3") (pintype "passive"))
    )
    (net (code "51") (name "2E3") (class "Default")
      (node (ref "J5") (pin "E3") (pinfunction "E3_E3") (pintype "bidirectional"))
      (node (ref "RN18") (pin "7") (pinfunction "2_7") (pintype "passive"))
      (node (ref "RN22") (pin "2") (pinfunction "1_2") (pintype "passive"))
    )
    (net (code "52") (name "2E6") (class "Default")
      (node (ref "J5") (pin "E6") (pinfunction "E6_E6") (pintype "bidirectional"))
      (node (ref "RN18") (pin "8") (pinfunction "2_8") (pintype "passive"))
      (node (ref "RN22") (pin "1") (pinfunction "1_1") (pintype "passive"))
    )
    (net (code "53") (name "2F1") (class "Default")
      (node (ref "J5") (pin "F1") (pinfunction "F1_F1") (pintype "bidirectional"))
      (node (ref "RN20") (pin "5") (pinfunction "2_5") (pintype "passive"))
      (node (ref "RN24") (pin "4") (pinfunction "1_4") (pintype "passive"))
    )
    (net (code "54") (name "2F2") (class "Default")
      (node (ref "J5") (pin "F2") (pinfunction "F2_F2") (pintype "bidirectional"))
      (node (ref "RN20") (pin "6") (pinfunction "2_6") (pintype "passive"))
      (node (ref "RN24") (pin "3") (pinfunction "1_3") (pintype "passive"))
    )
    (net (code "55") (name "2F3") (class "Default")
      (node (ref "J5") (pin "F3") (pinfunction "F3_F3") (pintype "bidirectional"))
      (node (ref "RN20") (pin "7") (pinfunction "2_7") (pintype "passive"))
      (node (ref "RN24") (pin "2") (pinfunction "1_2") (pintype "passive"))
    )
    (net (code "56") (name "2F6") (class "Default")
      (node (ref "J5") (pin "F6") (pinfunction "F6_F6") (pintype "bidirectional"))
      (node (ref "RN20") (pin "8") (pinfunction "2_8") (pintype "passive"))
      (node (ref "RN24") (pin "1") (pinfunction "1_1") (pintype "passive"))
    )
    (net (code "57") (name "2G1") (class "Default")
      (node (ref "J5") (pin "G1") (pinfunction "G1_G1") (pintype "bidirectional"))
      (node (ref "RN26") (pin "5") (pinfunction "2_5") (pintype "passive"))
      (node (ref "RN30") (pin "4") (pinfunction "1_4") (pintype "passive"))
    )
    (net (code "58") (name "2G2") (class "Default")
      (node (ref "J5") (pin "G2") (pinfunction "G2_G2") (pintype "bidirectional"))
      (node (ref "RN26") (pin "6") (pinfunction "2_6") (pintype "passive"))
      (node (ref "RN30") (pin "3") (pinfunction "1_3") (pintype "passive"))
    )
    (net (code "59") (name "2G3") (class "Default")
      (node (ref "J5") (pin "G3") (pinfunction "G3_G3") (pintype "bidirectional"))
      (node (ref "RN26") (pin "7") (pinfunction "2_7") (pintype "passive"))
      (node (ref "RN30") (pin "2") (pinfunction "1_2") (pintype "passive"))
    )
    (net (code "60") (name "2G6") (class "Default")
      (node (ref "J5") (pin "G6") (pinfunction "G6_G6") (pintype "bidirectional"))
      (node (ref "RN26") (pin "8") (pinfunction "2_8") (pintype "passive"))
      (node (ref "RN30") (pin "1") (pinfunction "1_1") (pintype "passive"))
    )
    (net (code "61") (name "2H1") (class "Default")
      (node (ref "J5") (pin "H1") (pinfunction "H1_H1") (pintype "bidirectional"))
      (node (ref "RN28") (pin "5") (pinfunction "2_5") (pintype "passive"))
      (node (ref "RN32") (pin "4") (pinfunction "1_4") (pintype "passive"))
    )
    (net (code "62") (name "2H2") (class "Default")
      (node (ref "J5") (pin "H2") (pinfunction "H2_H2") (pintype "bidirectional"))
      (node (ref "RN28") (pin "6") (pinfunction "2_6") (pintype "passive"))
      (node (ref "RN32") (pin "3") (pinfunction "1_3") (pintype "passive"))
    )
    (net (code "63") (name "2H3") (class "Default")
      (node (ref "J5") (pin "H3") (pinfunction "H3_H3") (pintype "bidirectional"))
      (node (ref "RN28") (pin "7") (pinfunction "2_7") (pintype "passive"))
      (node (ref "RN32") (pin "2") (pinfunction "1_2") (pintype "passive"))
    )
    (net (code "64") (name "2H6") (class "Default")
      (node (ref "J5") (pin "H6") (pinfunction "H6_H6") (pintype "bidirectional"))
      (node (ref "RN28") (pin "8") (pinfunction "2_8") (pintype "passive"))
      (node (ref "RN32") (pin "1") (pinfunction "1_1") (pintype "passive"))
    )
    (net (code "65") (name "GND") (class "Default")
      (node (ref "C1") (pin "2") (pinfunction "2_2") (pintype "passive"))
      (node (ref "C2") (pin "2") (pinfunction "2_2") (pintype "passive"))
      (node (ref "C3") (pin "2") (pinfunction "2_2") (pintype "passive"))
      (node (ref "C4") (pin "2") (pinfunction "2_2") (pintype "passive"))
      (node (ref "C7") (pin "-") (pinfunction "-_-") (pintype "passive"))
      (node (ref "C8") (pin "-") (pinfunction "-_-") (pintype "passive"))
      (node (ref "IC1") (pin "10") (pinfunction "VSS_10") (pintype "power_in"))
      (node (ref "IC2") (pin "10") (pinfunction "VSS_10") (pintype "power_in"))
      (node (ref "IC3") (pin "10") (pinfunction "VSS_10") (pintype "power_in"))
      (node (ref "IC4") (pin "10") (pinfunction "VSS_10") (pintype "power_in"))
      (node (ref "J1") (pin "4") (pinfunction "4_4") (pintype "passive"))
      (node (ref "J2") (pin "4") (pinfunction "4_4") (pintype "passive"))
      (node (ref "J4") (pin "A7") (pinfunction "A7_A7") (pintype "bidirectional"))
      (node (ref "J4") (pin "A8") (pinfunction "A8_A8") (pintype "bidirectional"))
      (node (ref "J4") (pin "B7") (pinfunction "B7_B7") (pintype "bidirectional"))
      (node (ref "J4") (pin "B8") (pinfunction "B8_B8") (pintype "bidirectional"))
      (node (ref "J4") (pin "C7") (pinfunction "C7_C7") (pintype "bidirectional"))
      (node (ref "J4") (pin "C8") (pinfunction "C8_C8") (pintype "bidirectional"))
      (node (ref "J4") (pin "D7") (pinfunction "D7_D7") (pintype "bidirectional"))
      (node (ref "J4") (pin "D8") (pinfunction "D8_D8") (pintype "bidirectional"))
      (node (ref "J4") (pin "E7") (pinfunction "E7_E7") (pintype "bidirectional"))
      (node (ref "J4") (pin "E8") (pinfunction "E8_E8") (pintype "bidirectional"))
      (node (ref "J4") (pin "F7") (pinfunction "F7_F7") (pintype "bidirectional"))
      (node (ref "J4") (pin "F8") (pinfunction "F8_F8") (pintype "bidirectional"))
      (node (ref "J4") (pin "G7") (pinfunction "G7_G7") (pintype "bidirectional"))
      (node (ref "J4") (pin "G8") (pinfunction "G8_G8") (pintype "bidirectional"))
      (node (ref "J4") (pin "GND0") (pinfunction "GND0_GND0") (pintype "power_in"))
      (node (ref "J4") (pin "GND1") (pinfunction "GND1_GND1") (pintype "power_in"))
      (node (ref "J4") (pin "GND2") (pinfunction "GND2_GND2") (pintype "power_in"))
      (node (ref "J4") (pin "GND3") (pinfunction "GND3_GND3") (pintype "power_in"))
      (node (ref "J4") (pin "GND4") (pinfunction "GND4_GND4") (pintype "power_in"))
      (node (ref "J4") (pin "GND5") (pinfunction "GND5_GND5") (pintype "power_in"))
      (node (ref "J4") (pin "H7") (pinfunction "H7_H7") (pintype "bidirectional"))
      (node (ref "J4") (pin "H8") (pinfunction "H8_H8") (pintype "bidirectional"))
      (node (ref "J5") (pin "A7") (pinfunction "A7_A7") (pintype "bidirectional"))
      (node (ref "J5") (pin "A8") (pinfunction "A8_A8") (pintype "bidirectional"))
      (node (ref "J5") (pin "B7") (pinfunction "B7_B7") (pintype "bidirectional"))
      (node (ref "J5") (pin "B8") (pinfunction "B8_B8") (pintype "bidirectional"))
      (node (ref "J5") (pin "C7") (pinfunction "C7_C7") (pintype "bidirectional"))
      (node (ref "J5") (pin "C8") (pinfunction "C8_C8") (pintype "bidirectional"))
      (node (ref "J5") (pin "D7") (pinfunction "D7_D7") (pintype "bidirectional"))
      (node (ref "J5") (pin "D8") (pinfunction "D8_D8") (pintype "bidirectional"))
      (node (ref "J5") (pin "E7") (pinfunction "E7_E7") (pintype "bidirectional"))
      (node (ref "J5") (pin "E8") (pinfunction "E8_E8") (pintype "bidirectional"))
      (node (ref "J5") (pin "F7") (pinfunction "F7_F7") (pintype "bidirectional"))
      (node (ref "J5") (pin "F8") (pinfunction "F8_F8") (pintype "bidirectional"))
      (node (ref "J5") (pin "G7") (pinfunction "G7_G7") (pintype "bidirectional"))
      (node (ref "J5") (pin "G8") (pinfunction "G8_G8") (pintype "bidirectional"))
      (node (ref "J5") (pin "GND0") (pinfunction "GND0_GND0") (pintype "power_in"))
      (node (ref "J5") (pin "GND1") (pinfunction "GND1_GND1") (pintype "power_in"))
      (node (ref "J5") (pin "GND2") (pinfunction "GND2_GND2") (pintype "power_in"))
      (node (ref "J5") (pin "GND3") (pinfunction "GND3_GND3") (pintype "power_in"))
      (node (ref "J5") (pin "GND4") (pinfunction "GND4_GND4") (pintype "power_in"))
      (node (ref "J5") (pin "GND5") (pinfunction "GND5_GND5") (pintype "power_in"))
      (node (ref "J5") (pin "H7") (pinfunction "H7_H7") (pintype "bidirectional"))
      (node (ref "J5") (pin "H8") (pinfunction "H8_H8") (pintype "bidirectional"))
      (node (ref "LED1") (pin "C") (pinfunction "C_C") (pintype "passive"))
      (node (ref "LED2") (pin "C") (pinfunction "C_C") (pintype "passive"))
      (node (ref "RN49") (pin "1") (pinfunction "1_1") (pintype "passive"))
      (node (ref "RN49") (pin "2") (pinfunction "1_2") (pintype "passive"))
      (node (ref "RN49") (pin "3") (pinfunction "1_3") (pintype "passive"))
      (node (ref "RN49") (pin "4") (pinfunction "1_4") (pintype "passive"))
      (node (ref "RN50") (pin "1") (pinfunction "1_1") (pintype "passive"))
      (node (ref "RN50") (pin "2") (pinfunction "1_2") (pintype "passive"))
      (node (ref "RN50") (pin "3") (pinfunction "1_3") (pintype "passive"))
      (node (ref "RN50") (pin "4") (pinfunction "1_4") (pintype "passive"))
      (node (ref "RN51") (pin "1") (pinfunction "1_1") (pintype "passive"))
      (node (ref "RN51") (pin "2") (pinfunction "1_2") (pintype "passive"))
      (node (ref "RN51") (pin "3") (pinfunction "1_3") (pintype "passive"))
      (node (ref "RN51") (pin "4") (pinfunction "1_4") (pintype "passive"))
      (node (ref "RN52") (pin "1") (pinfunction "1_1") (pintype "passive"))
      (node (ref "RN52") (pin "2") (pinfunction "1_2") (pintype "passive"))
      (node (ref "RN52") (pin "3") (pinfunction "1_3") (pintype "passive"))
      (node (ref "RN52") (pin "4") (pinfunction "1_4") (pintype "passive"))
    )
    (net (code "66") (name "GPA0-1") (class "Default")
      (node (ref "IC1") (pin "21") (pinfunction "GPA0_21") (pintype "bidirectional"))
      (node (ref "RN1") (pin "4") (pinfunction "1_4") (pintype "passive"))
    )
    (net (code "67") (name "GPA0-2") (class "Default")
      (node (ref "IC2") (pin "21") (pinfunction "GPA0_21") (pintype "bidirectional"))
      (node (ref "RN9") (pin "4") (pinfunction "1_4") (pintype "passive"))
    )
    (net (code "68") (name "GPA0-3") (class "Default")
      (node (ref "IC3") (pin "21") (pinfunction "GPA0_21") (pintype "bidirectional"))
      (node (ref "RN17") (pin "4") (pinfunction "1_4") (pintype "passive"))
    )
    (net (code "69") (name "GPA0-4") (class "Default")
      (node (ref "IC4") (pin "21") (pinfunction "GPA0_21") (pintype "bidirectional"))
      (node (ref "RN25") (pin "4") (pinfunction "1_4") (pintype "passive"))
    )
    (net (code "70") (name "GPA1-1") (class "Default")
      (node (ref "IC1") (pin "22") (pinfunction "GPA1_22") (pintype "bidirectional"))
      (node (ref "RN1") (pin "3") (pinfunction "1_3") (pintype "passive"))
    )
    (net (code "71") (name "GPA1-2") (class "Default")
      (node (ref "IC2") (pin "22") (pinfunction "GPA1_22") (pintype "bidirectional"))
      (node (ref "RN9") (pin "3") (pinfunction "1_3") (pintype "passive"))
    )
    (net (code "72") (name "GPA1-3") (class "Default")
      (node (ref "IC3") (pin "22") (pinfunction "GPA1_22") (pintype "bidirectional"))
      (node (ref "RN17") (pin "3") (pinfunction "1_3") (pintype "passive"))
    )
    (net (code "73") (name "GPA1-4") (class "Default")
      (node (ref "IC4") (pin "22") (pinfunction "GPA1_22") (pintype "bidirectional"))
      (node (ref "RN25") (pin "3") (pinfunction "1_3") (pintype "passive"))
    )
    (net (code "74") (name "GPA2-1") (class "Default")
      (node (ref "IC1") (pin "23") (pinfunction "GPA2_23") (pintype "bidirectional"))
      (node (ref "RN1") (pin "2") (pinfunction "1_2") (pintype "passive"))
    )
    (net (code "75") (name "GPA2-2") (class "Default")
      (node (ref "IC2") (pin "23") (pinfunction "GPA2_23") (pintype "bidirectional"))
      (node (ref "RN9") (pin "2") (pinfunction "1_2") (pintype "passive"))
    )
    (net (code "76") (name "GPA2-3") (class "Default")
      (node (ref "IC3") (pin "23") (pinfunction "GPA2_23") (pintype "bidirectional"))
      (node (ref "RN17") (pin "2") (pinfunction "1_2") (pintype "passive"))
    )
    (net (code "77") (name "GPA2-4") (class "Default")
      (node (ref "IC4") (pin "23") (pinfunction "GPA2_23") (pintype "bidirectional"))
      (node (ref "RN25") (pin "2") (pinfunction "1_2") (pintype "passive"))
    )
    (net (code "78") (name "GPA3-1") (class "Default")
      (node (ref "IC1") (pin "24") (pinfunction "GPA3_24") (pintype "bidirectional"))
      (node (ref "RN1") (pin "1") (pinfunction "1_1") (pintype "passive"))
    )
    (net (code "79") (name "GPA3-2") (class "Default")
      (node (ref "IC2") (pin "24") (pinfunction "GPA3_24") (pintype "bidirectional"))
      (node (ref "RN9") (pin "1") (pinfunction "1_1") (pintype "passive"))
    )
    (net (code "80") (name "GPA3-3") (class "Default")
      (node (ref "IC3") (pin "24") (pinfunction "GPA3_24") (pintype "bidirectional"))
      (node (ref "RN17") (pin "1") (pinfunction "1_1") (pintype "passive"))
    )
    (net (code "81") (name "GPA3-4") (class "Default")
      (node (ref "IC4") (pin "24") (pinfunction "GPA3_24") (pintype "bidirectional"))
      (node (ref "RN25") (pin "1") (pinfunction "1_1") (pintype "passive"))
    )
    (net (code "82") (name "GPA4-1") (class "Default")
      (node (ref "IC1") (pin "25") (pinfunction "GPA4_25") (pintype "bidirectional"))
      (node (ref "RN2") (pin "4") (pinfunction "1_4") (pintype "passive"))
    )
    (net (code "83") (name "GPA4-2") (class "Default")
      (node (ref "IC2") (pin "25") (pinfunction "GPA4_25") (pintype "bidirectional"))
      (node (ref "RN10") (pin "4") (pinfunction "1_4") (pintype "passive"))
    )
    (net (code "84") (name "GPA4-3") (class "Default")
      (node (ref "IC3") (pin "25") (pinfunction "GPA4_25") (pintype "bidirectional"))
      (node (ref "RN18") (pin "4") (pinfunction "1_4") (pintype "passive"))
    )
    (net (code "85") (name "GPA4-4") (class "Default")
      (node (ref "IC4") (pin "25") (pinfunction "GPA4_25") (pintype "bidirectional"))
      (node (ref "RN26") (pin "4") (pinfunction "1_4") (pintype "passive"))
    )
    (net (code "86") (name "GPA5-1") (class "Default")
      (node (ref "IC1") (pin "26") (pinfunction "GPA5_26") (pintype "bidirectional"))
      (node (ref "RN2") (pin "3") (pinfunction "1_3") (pintype "passive"))
    )
    (net (code "87") (name "GPA5-2") (class "Default")
      (node (ref "IC2") (pin "26") (pinfunction "GPA5_26") (pintype "bidirectional"))
      (node (ref "RN10") (pin "3") (pinfunction "1_3") (pintype "passive"))
    )
    (net (code "88") (name "GPA5-3") (class "Default")
      (node (ref "IC3") (pin "26") (pinfunction "GPA5_26") (pintype "bidirectional"))
      (node (ref "RN18") (pin "3") (pinfunction "1_3") (pintype "passive"))
    )
    (net (code "89") (name "GPA5-4") (class "Default")
      (node (ref "IC4") (pin "26") (pinfunction "GPA5_26") (pintype "bidirectional"))
      (node (ref "RN26") (pin "3") (pinfunction "1_3") (pintype "passive"))
    )
    (net (code "90") (name "GPA6-1") (class "Default")
      (node (ref "IC1") (pin "27") (pinfunction "GPA6_27") (pintype "bidirectional"))
      (node (ref "RN2") (pin "2") (pinfunction "1_2") (pintype "passive"))
    )
    (net (code "91") (name "GPA6-2") (class "Default")
      (node (ref "IC2") (pin "27") (pinfunction "GPA6_27") (pintype "bidirectional"))
      (node (ref "RN10") (pin "2") (pinfunction "1_2") (pintype "passive"))
    )
    (net (code "92") (name "GPA6-3") (class "Default")
      (node (ref "IC3") (pin "27") (pinfunction "GPA6_27") (pintype "bidirectional"))
      (node (ref "RN18") (pin "2") (pinfunction "1_2") (pintype "passive"))
    )
    (net (code "93") (name "GPA6-4") (class "Default")
      (node (ref "IC4") (pin "27") (pinfunction "GPA6_27") (pintype "bidirectional"))
      (node (ref "RN26") (pin "2") (pinfunction "1_2") (pintype "passive"))
    )
    (net (code "94") (name "GPA7-1") (class "Default")
      (node (ref "IC1") (pin "28") (pinfunction "GPA7_28") (pintype "bidirectional"))
      (node (ref "RN2") (pin "1") (pinfunction "1_1") (pintype "passive"))
    )
    (net (code "95") (name "GPA7-2") (class "Default")
      (node (ref "IC2") (pin "28") (pinfunction "GPA7_28") (pintype "bidirectional"))
      (node (ref "RN10") (pin "1") (pinfunction "1_1") (pintype "passive"))
    )
    (net (code "96") (name "GPA7-3") (class "Default")
      (node (ref "IC3") (pin "28") (pinfunction "GPA7_28") (pintype "bidirectional"))
      (node (ref "RN18") (pin "1") (pinfunction "1_1") (pintype "passive"))
    )
    (net (code "97") (name "GPA7-4") (class "Default")
      (node (ref "IC4") (pin "28") (pinfunction "GPA7_28") (pintype "bidirectional"))
      (node (ref "RN26") (pin "1") (pinfunction "1_1") (pintype "passive"))
    )
    (net (code "98") (name "GPB0-1") (class "Default")
      (node (ref "IC1") (pin "1") (pinfunction "GPB0_1") (pintype "bidirectional"))
      (node (ref "RN3") (pin "4") (pinfunction "1_4") (pintype "passive"))
    )
    (net (code "99") (name "GPB0-2") (class "Default")
      (node (ref "IC2") (pin "1") (pinfunction "GPB0_1") (pintype "bidirectional"))
      (node (ref "RN11") (pin "4") (pinfunction "1_4") (pintype "passive"))
    )
    (net (code "100") (name "GPB0-3") (class "Default")
      (node (ref "IC3") (pin "1") (pinfunction "GPB0_1") (pintype "bidirectional"))
      (node (ref "RN19") (pin "4") (pinfunction "1_4") (pintype "passive"))
    )
    (net (code "101") (name "GPB0-4") (class "Default")
      (node (ref "IC4") (pin "1") (pinfunction "GPB0_1") (pintype "bidirectional"))
      (node (ref "RN27") (pin "4") (pinfunction "1_4") (pintype "passive"))
    )
    (net (code "102") (name "GPB1-1") (class "Default")
      (node (ref "IC1") (pin "2") (pinfunction "GPB1_2") (pintype "bidirectional"))
      (node (ref "RN3") (pin "3") (pinfunction "1_3") (pintype "passive"))
    )
    (net (code "103") (name "GPB1-2") (class "Default")
      (node (ref "IC2") (pin "2") (pinfunction "GPB1_2") (pintype "bidirectional"))
      (node (ref "RN11") (pin "3") (pinfunction "1_3") (pintype "passive"))
    )
    (net (code "104") (name "GPB1-3") (class "Default")
      (node (ref "IC3") (pin "2") (pinfunction "GPB1_2") (pintype "bidirectional"))
      (node (ref "RN19") (pin "3") (pinfunction "1_3") (pintype "passive"))
    )
    (net (code "105") (name "GPB1-4") (class "Default")
      (node (ref "IC4") (pin "2") (pinfunction "GPB1_2") (pintype "bidirectional"))
      (node (ref "RN27") (pin "3") (pinfunction "1_3") (pintype "passive"))
    )
    (net (code "106") (name "GPB2-1") (class "Default")
      (node (ref "IC1") (pin "3") (pinfunction "GPB2_3") (pintype "bidirectional"))
      (node (ref "RN3") (pin "2") (pinfunction "1_2") (pintype "passive"))
    )
    (net (code "107") (name "GPB2-2") (class "Default")
      (node (ref "IC2") (pin "3") (pinfunction "GPB2_3") (pintype "bidirectional"))
      (node (ref "RN11") (pin "2") (pinfunction "1_2") (pintype "passive"))
    )
    (net (code "108") (name "GPB2-3") (class "Default")
      (node (ref "IC3") (pin "3") (pinfunction "GPB2_3") (pintype "bidirectional"))
      (node (ref "RN19") (pin "2") (pinfunction "1_2") (pintype "passive"))
    )
    (net (code "109") (name "GPB2-4") (class "Default")
      (node (ref "IC4") (pin "3") (pinfunction "GPB2_3") (pintype "bidirectional"))
      (node (ref "RN27") (pin "2") (pinfunction "1_2") (pintype "passive"))
    )
    (net (code "110") (name "GPB3-1") (class "Default")
      (node (ref "IC1") (pin "4") (pinfunction "GPB3_4") (pintype "bidirectional"))
      (node (ref "RN3") (pin "1") (pinfunction "1_1") (pintype "passive"))
    )
    (net (code "111") (name "GPB3-2") (class "Default")
      (node (ref "IC2") (pin "4") (pinfunction "GPB3_4") (pintype "bidirectional"))
      (node (ref "RN11") (pin "1") (pinfunction "1_1") (pintype "passive"))
    )
    (net (code "112") (name "GPB3-3") (class "Default")
      (node (ref "IC3") (pin "4") (pinfunction "GPB3_4") (pintype "bidirectional"))
      (node (ref "RN19") (pin "1") (pinfunction "1_1") (pintype "passive"))
    )
    (net (code "113") (name "GPB3-4") (class "Default")
      (node (ref "IC4") (pin "4") (pinfunction "GPB3_4") (pintype "bidirectional"))
      (node (ref "RN27") (pin "1") (pinfunction "1_1") (pintype "passive"))
    )
    (net (code "114") (name "GPB4-1") (class "Default")
      (node (ref "IC1") (pin "5") (pinfunction "GPB4_5") (pintype "bidirectional"))
      (node (ref "RN4") (pin "4") (pinfunction "1_4") (pintype "passive"))
    )
    (net (code "115") (name "GPB4-2") (class "Default")
      (node (ref "IC2") (pin "5") (pinfunction "GPB4_5") (pintype "bidirectional"))
      (node (ref "RN12") (pin "4") (pinfunction "1_4") (pintype "passive"))
    )
    (net (code "116") (name "GPB4-3") (class "Default")
      (node (ref "IC3") (pin "5") (pinfunction "GPB4_5") (pintype "bidirectional"))
      (node (ref "RN20") (pin "4") (pinfunction "1_4") (pintype "passive"))
    )
    (net (code "117") (name "GPB4-4") (class "Default")
      (node (ref "IC4") (pin "5") (pinfunction "GPB4_5") (pintype "bidirectional"))
      (node (ref "RN28") (pin "4") (pinfunction "1_4") (pintype "passive"))
    )
    (net (code "118") (name "GPB5-1") (class "Default")
      (node (ref "IC1") (pin "6") (pinfunction "GPB5_6") (pintype "bidirectional"))
      (node (ref "RN4") (pin "3") (pinfunction "1_3") (pintype "passive"))
    )
    (net (code "119") (name "GPB5-2") (class "Default")
      (node (ref "IC2") (pin "6") (pinfunction "GPB5_6") (pintype "bidirectional"))
      (node (ref "RN12") (pin "3") (pinfunction "1_3") (pintype "passive"))
    )
    (net (code "120") (name "GPB5-3") (class "Default")
      (node (ref "IC3") (pin "6") (pinfunction "GPB5_6") (pintype "bidirectional"))
      (node (ref "RN20") (pin "3") (pinfunction "1_3") (pintype "passive"))
    )
    (net (code "121") (name "GPB5-4") (class "Default")
      (node (ref "IC4") (pin "6") (pinfunction "GPB5_6") (pintype "bidirectional"))
      (node (ref "RN28") (pin "3") (pinfunction "1_3") (pintype "passive"))
    )
    (net (code "122") (name "GPB6-1") (class "Default")
      (node (ref "IC1") (pin "7") (pinfunction "GPB6_7") (pintype "bidirectional"))
      (node (ref "RN4") (pin "2") (pinfunction "1_2") (pintype "passive"))
    )
    (net (code "123") (name "GPB6-2") (class "Default")
      (node (ref "IC2") (pin "7") (pinfunction "GPB6_7") (pintype "bidirectional"))
      (node (ref "RN12") (pin "2") (pinfunction "1_2") (pintype "passive"))
    )
    (net (code "124") (name "GPB6-3") (class "Default")
      (node (ref "IC3") (pin "7") (pinfunction "GPB6_7") (pintype "bidirectional"))
      (node (ref "RN20") (pin "2") (pinfunction "1_2") (pintype "passive"))
    )
    (net (code "125") (name "GPB6-4") (class "Default")
      (node (ref "IC4") (pin "7") (pinfunction "GPB6_7") (pintype "bidirectional"))
      (node (ref "RN28") (pin "2") (pinfunction "1_2") (pintype "passive"))
    )
    (net (code "126") (name "GPB7-1") (class "Default")
      (node (ref "IC1") (pin "8") (pinfunction "GPB7_8") (pintype "bidirectional"))
      (node (ref "RN4") (pin "1") (pinfunction "1_1") (pintype "passive"))
    )
    (net (code "127") (name "GPB7-2") (class "Default")
      (node (ref "IC2") (pin "8") (pinfunction "GPB7_8") (pintype "bidirectional"))
      (node (ref "RN12") (pin "1") (pinfunction "1_1") (pintype "passive"))
    )
    (net (code "128") (name "GPB7-3") (class "Default")
      (node (ref "IC3") (pin "8") (pinfunction "GPB7_8") (pintype "bidirectional"))
      (node (ref "RN20") (pin "1") (pinfunction "1_1") (pintype "passive"))
    )
    (net (code "129") (name "GPB7-4") (class "Default")
      (node (ref "IC4") (pin "8") (pinfunction "GPB7_8") (pintype "bidirectional"))
      (node (ref "RN28") (pin "1") (pinfunction "1_1") (pintype "passive"))
    )
    (net (code "130") (name "Net-(IC1-A0)") (class "Default")
      (node (ref "IC1") (pin "15") (pinfunction "A0_15") (pintype "input"))
      (node (ref "J7") (pin "2") (pinfunction "2_2") (pintype "passive"))
      (node (ref "RN49") (pin "6") (pinfunction "2_6") (pintype "passive"))
    )
    (net (code "131") (name "Net-(IC1-A1)") (class "Default")
      (node (ref "IC1") (pin "16") (pinfunction "A1_16") (pintype "input"))
      (node (ref "J7") (pin "4") (pinfunction "4_4") (pintype "passive"))
      (node (ref "RN49") (pin "7") (pinfunction "2_7") (pintype "passive"))
    )
    (net (code "132") (name "Net-(IC1-A2)") (class "Default")
      (node (ref "IC1") (pin "17") (pinfunction "A2_17") (pintype "input"))
      (node (ref "J7") (pin "6") (pinfunction "6_6") (pintype "passive"))
      (node (ref "RN49") (pin "8") (pinfunction "2_8") (pintype "passive"))
    )
    (net (code "133") (name "Net-(IC2-A0)") (class "Default")
      (node (ref "IC2") (pin "15") (pinfunction "A0_15") (pintype "input"))
      (node (ref "J12") (pin "2") (pinfunction "2_2") (pintype "passive"))
      (node (ref "RN50") (pin "6") (pinfunction "2_6") (pintype "passive"))
    )
    (net (code "134") (name "Net-(IC2-A1)") (class "Default")
      (node (ref "IC2") (pin "16") (pinfunction "A1_16") (pintype "input"))
      (node (ref "J12") (pin "4") (pinfunction "4_4") (pintype "passive"))
      (node (ref "RN50") (pin "7") (pinfunction "2_7") (pintype "passive"))
    )
    (net (code "135") (name "Net-(IC2-A2)") (class "Default")
      (node (ref "IC2") (pin "17") (pinfunction "A2_17") (pintype "input"))
      (node (ref "J12") (pin "6") (pinfunction "6_6") (pintype "passive"))
      (node (ref "RN50") (pin "8") (pinfunction "2_8") (pintype "passive"))
    )
    (net (code "136") (name "Net-(IC3-A0)") (class "Default")
      (node (ref "IC3") (pin "15") (pinfunction "A0_15") (pintype "input"))
      (node (ref "J11") (pin "2") (pinfunction "2_2") (pintype "passive"))
      (node (ref "RN51") (pin "6") (pinfunction "2_6") (pintype "passive"))
    )
    (net (code "137") (name "Net-(IC3-A1)") (class "Default")
      (node (ref "IC3") (pin "16") (pinfunction "A1_16") (pintype "input"))
      (node (ref "J11") (pin "4") (pinfunction "4_4") (pintype "passive"))
      (node (ref "RN51") (pin "7") (pinfunction "2_7") (pintype "passive"))
    )
    (net (code "138") (name "Net-(IC3-A2)") (class "Default")
      (node (ref "IC3") (pin "17") (pinfunction "A2_17") (pintype "input"))
      (node (ref "J11") (pin "6") (pinfunction "6_6") (pintype "passive"))
      (node (ref "RN51") (pin "8") (pinfunction "2_8") (pintype "passive"))
    )
    (net (code "139") (name "Net-(IC4-A0)") (class "Default")
      (node (ref "IC4") (pin "15") (pinfunction "A0_15") (pintype "input"))
      (node (ref "J10") (pin "2") (pinfunction "2_2") (pintype "passive"))
      (node (ref "RN52") (pin "6") (pinfunction "2_6") (pintype "passive"))
    )
    (net (code "140") (name "Net-(IC4-A1)") (class "Default")
      (node (ref "IC4") (pin "16") (pinfunction "A1_16") (pintype "input"))
      (node (ref "J10") (pin "4") (pinfunction "4_4") (pintype "passive"))
      (node (ref "RN52") (pin "7") (pinfunction "2_7") (pintype "passive"))
    )
    (net (code "141") (name "Net-(IC4-A2)") (class "Default")
      (node (ref "IC4") (pin "17") (pinfunction "A2_17") (pintype "input"))
      (node (ref "J10") (pin "6") (pinfunction "6_6") (pintype "passive"))
      (node (ref "RN52") (pin "8") (pinfunction "2_8") (pintype "passive"))
    )
    (net (code "142") (name "Net-(LED1-PadA)") (class "Default")
      (node (ref "LED1") (pin "A") (pinfunction "A_A") (pintype "passive"))
      (node (ref "R98") (pin "1") (pinfunction "1_1") (pintype "passive"))
    )
    (net (code "143") (name "Net-(LED2-PadA)") (class "Default")
      (node (ref "LED2") (pin "A") (pinfunction "A_A") (pintype "passive"))
      (node (ref "R97") (pin "1") (pinfunction "1_1") (pintype "passive"))
    )
    (net (code "144") (name "Net-(R99-Pad2)") (class "Default")
      (node (ref "R99") (pin "2") (pinfunction "2_2") (pintype "passive"))
      (node (ref "SJ2") (pin "1") (pinfunction "1_1") (pintype "passive"))
    )
    (net (code "145") (name "Net-(R100-Pad2)") (class "Default")
      (node (ref "R100") (pin "2") (pinfunction "2_2") (pintype "passive"))
      (node (ref "SJ1") (pin "1") (pinfunction "1_1") (pintype "passive"))
    )
    (net (code "146") (name "Net-(R101-Pad2)") (class "Default")
      (node (ref "R101") (pin "2") (pinfunction "2_2") (pintype "passive"))
      (node (ref "SJ3") (pin "1") (pinfunction "1_1") (pintype "passive"))
    )
    (net (code "147") (name "SCL") (class "Default")
      (node (ref "IC1") (pin "12") (pinfunction "SCL_12") (pintype "input"))
      (node (ref "IC2") (pin "12") (pinfunction "SCL_12") (pintype "input"))
      (node (ref "IC3") (pin "12") (pinfunction "SCL_12") (pintype "input"))
      (node (ref "IC4") (pin "12") (pinfunction "SCL_12") (pintype "input"))
      (node (ref "J1") (pin "1") (pinfunction "1_1") (pintype "passive"))
      (node (ref "J2") (pin "1") (pinfunction "1_1") (pintype "passive"))
      (node (ref "R99") (pin "1") (pinfunction "1_1") (pintype "passive"))
    )
    (net (code "148") (name "SDA") (class "Default")
      (node (ref "IC1") (pin "13") (pinfunction "SDA_13") (pintype "bidirectional"))
      (node (ref "IC2") (pin "13") (pinfunction "SDA_13") (pintype "bidirectional"))
      (node (ref "IC3") (pin "13") (pinfunction "SDA_13") (pintype "bidirectional"))
      (node (ref "IC4") (pin "13") (pinfunction "SDA_13") (pintype "bidirectional"))
      (node (ref "J1") (pin "2") (pinfunction "2_2") (pintype "passive"))
      (node (ref "J2") (pin "2") (pinfunction "2_2") (pintype "passive"))
      (node (ref "R100") (pin "1") (pinfunction "1_1") (pintype "passive"))
    )
    (net (code "149") (name "VCC") (class "Default")
      (node (ref "C1") (pin "1") (pinfunction "1_1") (pintype "passive"))
      (node (ref "C2") (pin "1") (pinfunction "1_1") (pintype "passive"))
      (node (ref "C3") (pin "1") (pinfunction "1_1") (pintype "passive"))
      (node (ref "C4") (pin "1") (pinfunction "1_1") (pintype "passive"))
      (node (ref "IC1") (pin "9") (pinfunction "VDD_9") (pintype "power_in"))
      (node (ref "IC2") (pin "9") (pinfunction "VDD_9") (pintype "power_in"))
      (node (ref "IC3") (pin "9") (pinfunction "VDD_9") (pintype "power_in"))
      (node (ref "IC4") (pin "9") (pinfunction "VDD_9") (pintype "power_in"))
      (node (ref "J1") (pin "5") (pinfunction "5_5") (pintype "passive"))
      (node (ref "J10") (pin "1") (pinfunction "1_1") (pintype "passive"))
      (node (ref "J10") (pin "3") (pinfunction "3_3") (pintype "passive"))
      (node (ref "J10") (pin "5") (pinfunction "5_5") (pintype "passive"))
      (node (ref "J11") (pin "1") (pinfunction "1_1") (pintype "passive"))
      (node (ref "J11") (pin "3") (pinfunction "3_3") (pintype "passive"))
      (node (ref "J11") (pin "5") (pinfunction "5_5") (pintype "passive"))
      (node (ref "J12") (pin "1") (pinfunction "1_1") (pintype "passive"))
      (node (ref "J12") (pin "3") (pinfunction "3_3") (pintype "passive"))
      (node (ref "J12") (pin "5") (pinfunction "5_5") (pintype "passive"))
      (node (ref "J2") (pin "5") (pinfunction "5_5") (pintype "passive"))
      (node (ref "J7") (pin "1") (pinfunction "1_1") (pintype "passive"))
      (node (ref "J7") (pin "3") (pinfunction "3_3") (pintype "passive"))
      (node (ref "J7") (pin "5") (pinfunction "5_5") (pintype "passive"))
      (node (ref "R97") (pin "2") (pinfunction "2_2") (pintype "passive"))
      (node (ref "RN13") (pin "5") (pinfunction "2_5") (pintype "passive"))
      (node (ref "RN13") (pin "6") (pinfunction "2_6") (pintype "passive"))
      (node (ref "RN13") (pin "7") (pinfunction "2_7") (pintype "passive"))
      (node (ref "RN13") (pin "8") (pinfunction "2_8") (pintype "passive"))
      (node (ref "RN14") (pin "5") (pinfunction "2_5") (pintype "passive"))
      (node (ref "RN14") (pin "6") (pinfunction "2_6") (pintype "passive"))
      (node (ref "RN14") (pin "7") (pinfunction "2_7") (pintype "passive"))
      (node (ref "RN14") (pin "8") (pinfunction "2_8") (pintype "passive"))
      (node (ref "RN15") (pin "5") (pinfunction "2_5") (pintype "passive"))
      (node (ref "RN15") (pin "6") (pinfunction "2_6") (pintype "passive"))
      (node (ref "RN15") (pin "7") (pinfunction "2_7") (pintype "passive"))
      (node (ref "RN15") (pin "8") (pinfunction "2_8") (pintype "passive"))
      (node (ref "RN16") (pin "5") (pinfunction "2_5") (pintype "passive"))
      (node (ref "RN16") (pin "6") (pinfunction "2_6") (pintype "passive"))
      (node (ref "RN16") (pin "7") (pinfunction "2_7") (pintype "passive"))
      (node (ref "RN16") (pin "8") (pinfunction "2_8") (pintype "passive"))
      (node (ref "RN21") (pin "5") (pinfunction "2_5") (pintype "passive"))
      (node (ref "RN21") (pin "6") (pinfunction "2_6") (pintype "passive"))
      (node (ref "RN21") (pin "7") (pinfunction "2_7") (pintype "passive"))
      (node (ref "RN21") (pin "8") (pinfunction "2_8") (pintype "passive"))
      (node (ref "RN22") (pin "5") (pinfunction "2_5") (pintype "passive"))
      (node (ref "RN22") (pin "6") (pinfunction "2_6") (pintype "passive"))
      (node (ref "RN22") (pin "7") (pinfunction "2_7") (pintype "passive"))
      (node (ref "RN22") (pin "8") (pinfunction "2_8") (pintype "passive"))
      (node (ref "RN23") (pin "5") (pinfunction "2_5") (pintype "passive"))
      (node (ref "RN23") (pin "6") (pinfunction "2_6") (pintype "passive"))
      (node (ref "RN23") (pin "7") (pinfunction "2_7") (pintype "passive"))
      (node (ref "RN23") (pin "8") (pinfunction "2_8") (pintype "passive"))
      (node (ref "RN24") (pin "5") (pinfunction "2_5") (pintype "passive"))
      (node (ref "RN24") (pin "6") (pinfunction "2_6") (pintype "passive"))
      (node (ref "RN24") (pin "7") (pinfunction "2_7") (pintype "passive"))
      (node (ref "RN24") (pin "8") (pinfunction "2_8") (pintype "passive"))
      (node (ref "RN29") (pin "5") (pinfunction "2_5") (pintype "passive"))
      (node (ref "RN29") (pin "6") (pinfunction "2_6") (pintype "passive"))
      (node (ref "RN29") (pin "7") (pinfunction "2_7") (pintype "passive"))
      (node (ref "RN29") (pin "8") (pinfunction "2_8") (pintype "passive"))
      (node (ref "RN30") (pin "5") (pinfunction "2_5") (pintype "passive"))
      (node (ref "RN30") (pin "6") (pinfunction "2_6") (pintype "passive"))
      (node (ref "RN30") (pin "7") (pinfunction "2_7") (pintype "passive"))
      (node (ref "RN30") (pin "8") (pinfunction "2_8") (pintype "passive"))
      (node (ref "RN31") (pin "5") (pinfunction "2_5") (pintype "passive"))
      (node (ref "RN31") (pin "6") (pinfunction "2_6") (pintype "passive"))
      (node (ref "RN31") (pin "7") (pinfunction "2_7") (pintype "passive"))
      (node (ref "RN31") (pin "8") (pinfunction "2_8") (pintype "passive"))
      (node (ref "RN32") (pin "5") (pinfunction "2_5") (pintype "passive"))
      (node (ref "RN32") (pin "6") (pinfunction "2_6") (pintype "passive"))
      (node (ref "RN32") (pin "7") (pinfunction "2_7") (pintype "passive"))
      (node (ref "RN32") (pin "8") (pinfunction "2_8") (pintype "passive"))
      (node (ref "RN5") (pin "5") (pinfunction "2_5") (pintype "passive"))
      (node (ref "RN5") (pin "6") (pinfunction "2_6") (pintype "passive"))
      (node (ref "RN5") (pin "7") (pinfunction "2_7") (pintype "passive"))
      (node (ref "RN5") (pin "8") (pinfunction "2_8") (pintype "passive"))
      (node (ref "RN6") (pin "5") (pinfunction "2_5") (pintype "passive"))
      (node (ref "RN6") (pin "6") (pinfunction "2_6") (pintype "passive"))
      (node (ref "RN6") (pin "7") (pinfunction "2_7") (pintype "passive"))
      (node (ref "RN6") (pin "8") (pinfunction "2_8") (pintype "passive"))
      (node (ref "RN7") (pin "5") (pinfunction "2_5") (pintype "passive"))
      (node (ref "RN7") (pin "6") (pinfunction "2_6") (pintype "passive"))
      (node (ref "RN7") (pin "7") (pinfunction "2_7") (pintype "passive"))
      (node (ref "RN7") (pin "8") (pinfunction "2_8") (pintype "passive"))
      (node (ref "RN8") (pin "5") (pinfunction "2_5") (pintype "passive"))
      (node (ref "RN8") (pin "6") (pinfunction "2_6") (pintype "passive"))
      (node (ref "RN8") (pin "7") (pinfunction "2_7") (pintype "passive"))
      (node (ref "RN8") (pin "8") (pinfunction "2_8") (pintype "passive"))
      (node (ref "SJ1") (pin "2") (pinfunction "2_2") (pintype "passive"))
      (node (ref "SJ2") (pin "2") (pinfunction "2_2") (pintype "passive"))
      (node (ref "SJ3") (pin "2") (pinfunction "2_2") (pintype "passive"))
    )
    (net (code "150") (name "VIN") (class "Default")
      (node (ref "C7") (pin "+") (pinfunction "+_+") (pintype "passive"))
      (node (ref "C8") (pin "+") (pinfunction "+_+") (pintype "passive"))
      (node (ref "J1") (pin "3") (pinfunction "3_3") (pintype "passive"))
      (node (ref "J2") (pin "3") (pinfunction "3_3") (pintype "passive"))
      (node (ref "J4") (pin "A4") (pinfunction "A4_A4") (pintype "bidirectional"))
      (node (ref "J4") (pin "A5") (pinfunction "A5_A5") (pintype "bidirectional"))
      (node (ref "J4") (pin "B4") (pinfunction "B4_B4") (pintype "bidirectional"))
      (node (ref "J4") (pin "B5") (pinfunction "B5_B5") (pintype "bidirectional"))
      (node (ref "J4") (pin "C4") (pinfunction "C4_C4") (pintype "bidirectional"))
      (node (ref "J4") (pin "C5") (pinfunction "C5_C5") (pintype "bidirectional"))
      (node (ref "J4") (pin "D4") (pinfunction "D4_D4") (pintype "bidirectional"))
      (node (ref "J4") (pin "D5") (pinfunction "D5_D5") (pintype "bidirectional"))
      (node (ref "J4") (pin "E4") (pinfunction "E4_E4") (pintype "bidirectional"))
      (node (ref "J4") (pin "E5") (pinfunction "E5_E5") (pintype "bidirectional"))
      (node (ref "J4") (pin "F4") (pinfunction "F4_F4") (pintype "bidirectional"))
      (node (ref "J4") (pin "F5") (pinfunction "F5_F5") (pintype "bidirectional"))
      (node (ref "J4") (pin "G4") (pinfunction "G4_G4") (pintype "bidirectional"))
      (node (ref "J4") (pin "G5") (pinfunction "G5_G5") (pintype "bidirectional"))
      (node (ref "J4") (pin "H4") (pinfunction "H4_H4") (pintype "bidirectional"))
      (node (ref "J4") (pin "H5") (pinfunction "H5_H5") (pintype "bidirectional"))
      (node (ref "J5") (pin "A4") (pinfunction "A4_A4") (pintype "bidirectional"))
      (node (ref "J5") (pin "A5") (pinfunction "A5_A5") (pintype "bidirectional"))
      (node (ref "J5") (pin "B4") (pinfunction "B4_B4") (pintype "bidirectional"))
      (node (ref "J5") (pin "B5") (pinfunction "B5_B5") (pintype "bidirectional"))
      (node (ref "J5") (pin "C4") (pinfunction "C4_C4") (pintype "bidirectional"))
      (node (ref "J5") (pin "C5") (pinfunction "C5_C5") (pintype "bidirectional"))
      (node (ref "J5") (pin "D4") (pinfunction "D4_D4") (pintype "bidirectional"))
      (node (ref "J5") (pin "D5") (pinfunction "D5_D5") (pintype "bidirectional"))
      (node (ref "J5") (pin "E4") (pinfunction "E4_E4") (pintype "bidirectional"))
      (node (ref "J5") (pin "E5") (pinfunction "E5_E5") (pintype "bidirectional"))
      (node (ref "J5") (pin "F4") (pinfunction "F4_F4") (pintype "bidirectional"))
      (node (ref "J5") (pin "F5") (pinfunction "F5_F5") (pintype "bidirectional"))
      (node (ref "J5") (pin "G4") (pinfunction "G4_G4") (pintype "bidirectional"))
      (node (ref "J5") (pin "G5") (pinfunction "G5_G5") (pintype "bidirectional"))
      (node (ref "J5") (pin "H4") (pinfunction "H4_H4") (pintype "bidirectional"))
      (node (ref "J5") (pin "H5") (pinfunction "H5_H5") (pintype "bidirectional"))
      (node (ref "R98") (pin "2") (pinfunction "2_2") (pintype "passive"))
    )
    (net (code "151") (name "unconnected-(IC1-INTB-Pad19)") (class "Default")
      (node (ref "IC1") (pin "19") (pinfunction "INTB_19") (pintype "output"))
    )
    (net (code "152") (name "unconnected-(IC2-INTB-Pad19)") (class "Default")
      (node (ref "IC2") (pin "19") (pinfunction "INTB_19") (pintype "output"))
    )
    (net (code "153") (name "unconnected-(IC3-INTB-Pad19)") (class "Default")
      (node (ref "IC3") (pin "19") (pinfunction "INTB_19") (pintype "output"))
    )
    (net (code "154") (name "unconnected-(IC4-INTB-Pad19)") (class "Default")
      (node (ref "IC4") (pin "19") (pinfunction "INTB_19") (pintype "output"))
    )
    (net (code "155") (name "unconnected-(RN49D-2-Pad5)") (class "Default")
      (node (ref "RN49") (pin "5") (pinfunction "2_5") (pintype "passive"))
    )
    (net (code "156") (name "unconnected-(RN50D-2-Pad5)") (class "Default")
      (node (ref "RN50") (pin "5") (pinfunction "2_5") (pintype "passive"))
    )
    (net (code "157") (name "unconnected-(RN51D-2-Pad5)") (class "Default")
      (node (ref "RN51") (pin "5") (pinfunction "2_5") (pintype "passive"))
    )
    (net (code "158") (name "unconnected-(RN52D-2-Pad5)") (class "Default")
      (node (ref "RN52") (pin "5") (pinfunction "2_5") (pintype "passive"))
    )
    (net (code "159") (name "~{INT}") (class "Default")
      (node (ref "IC1") (pin "20") (pinfunction "INTA_20") (pintype "output"))
      (node (ref "IC2") (pin "20") (pinfunction "INTA_20") (pintype "output"))
      (node (ref "IC3") (pin "20") (pinfunction "INTA_20") (pintype "output"))
      (node (ref "IC4") (pin "20") (pinfunction "INTA_20") (pintype "output"))
      (node (ref "J3") (pin "1") (pinfunction "1_1") (pintype "passive"))
    )
    (net (code "160") (name "~{RESET}") (class "Default")
      (node (ref "IC1") (pin "18") (pinfunction "~{RESET}_18") (pintype "input"))
      (node (ref "IC2") (pin "18") (pinfunction "~{RESET}_18") (pintype "input"))
      (node (ref "IC3") (pin "18") (pinfunction "~{RESET}_18") (pintype "input"))
      (node (ref "IC4") (pin "18") (pinfunction "~{RESET}_18") (pintype "input"))
      (node (ref "J1") (pin "6") (pinfunction "6_6") (pintype "passive"))
      (node (ref "J2") (pin "6") (pinfunction "6_6") (pintype "passive"))
      (node (ref "R101") (pin "1") (pinfunction "1_1") (pintype "passive"))
    )
  )
)
